# 20160428.net
KiCad netlist of a schematic drawn in Altium Designer
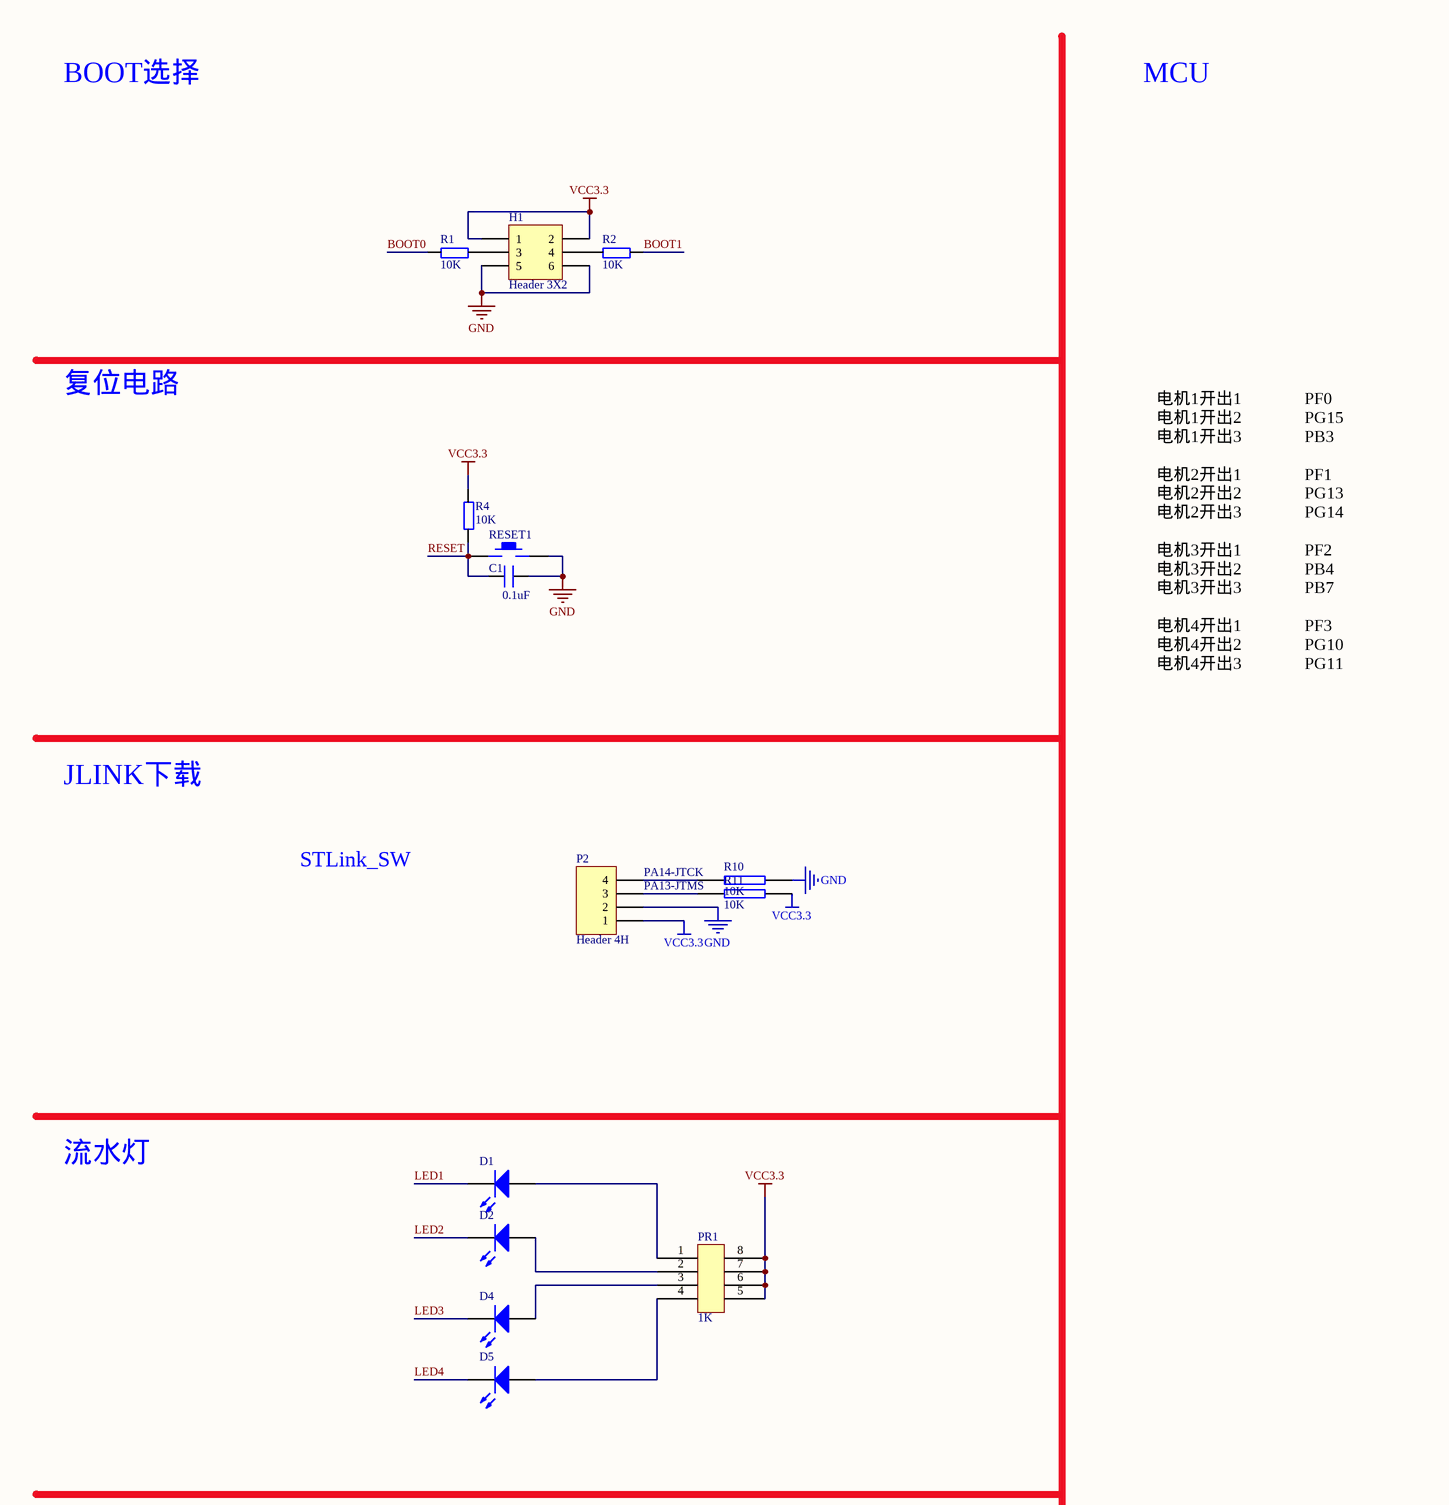
[diagram p0: 主控板20160428.SchDoc, top left]
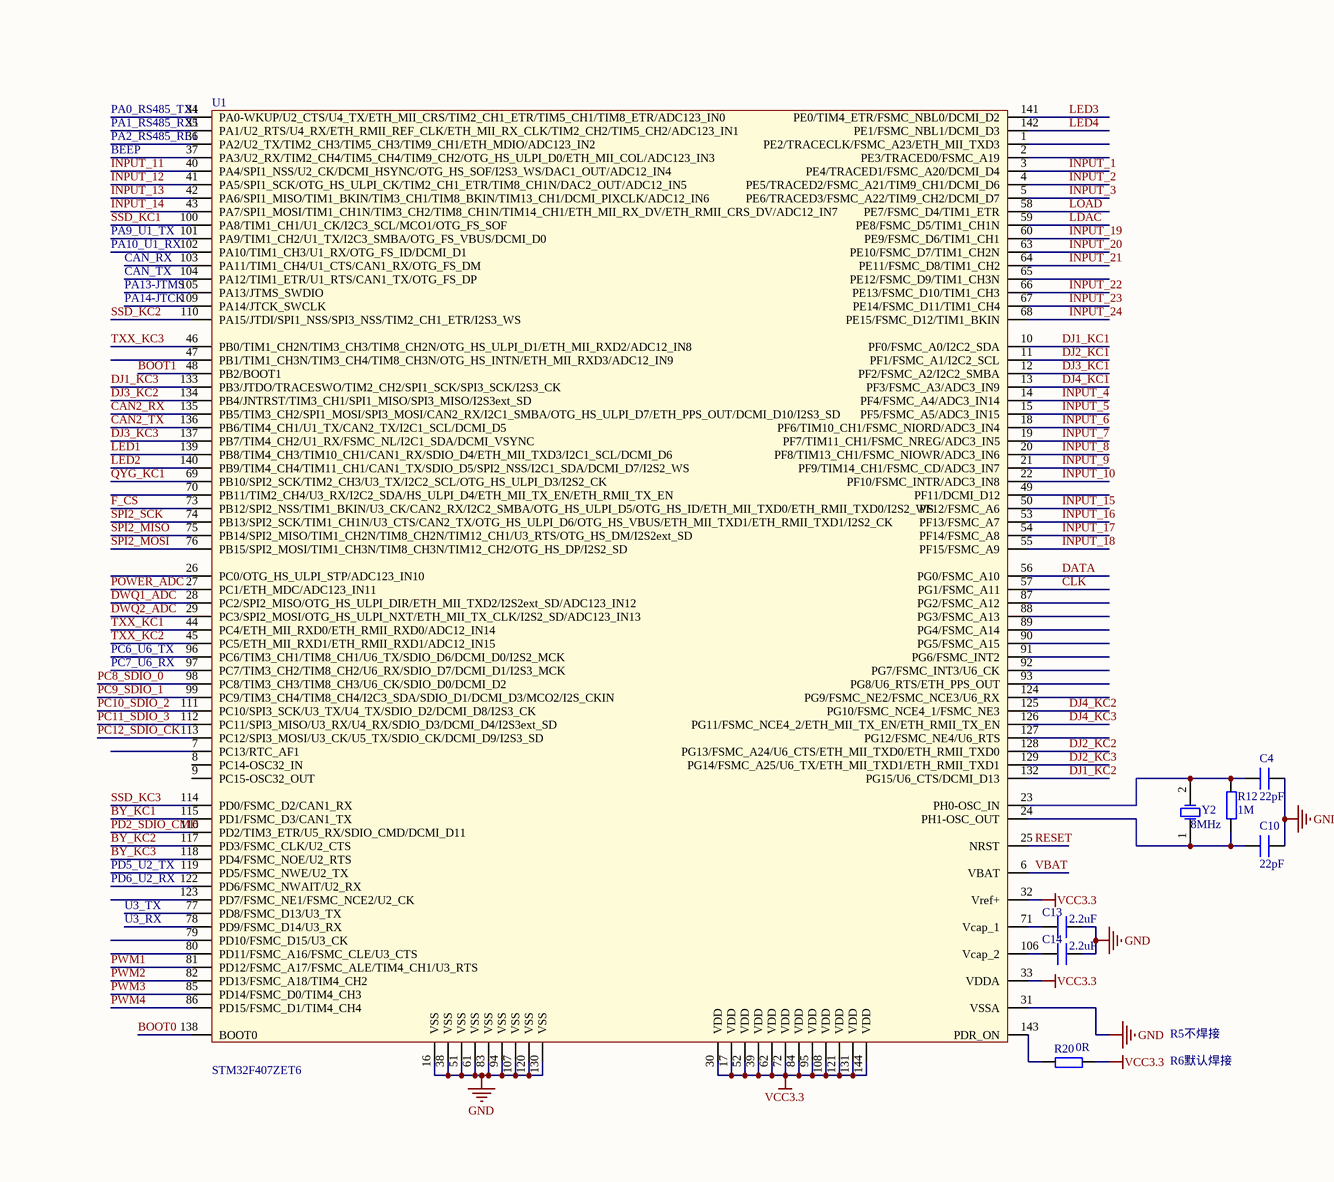
[diagram p1: 主控板20160428.SchDoc, top middle]
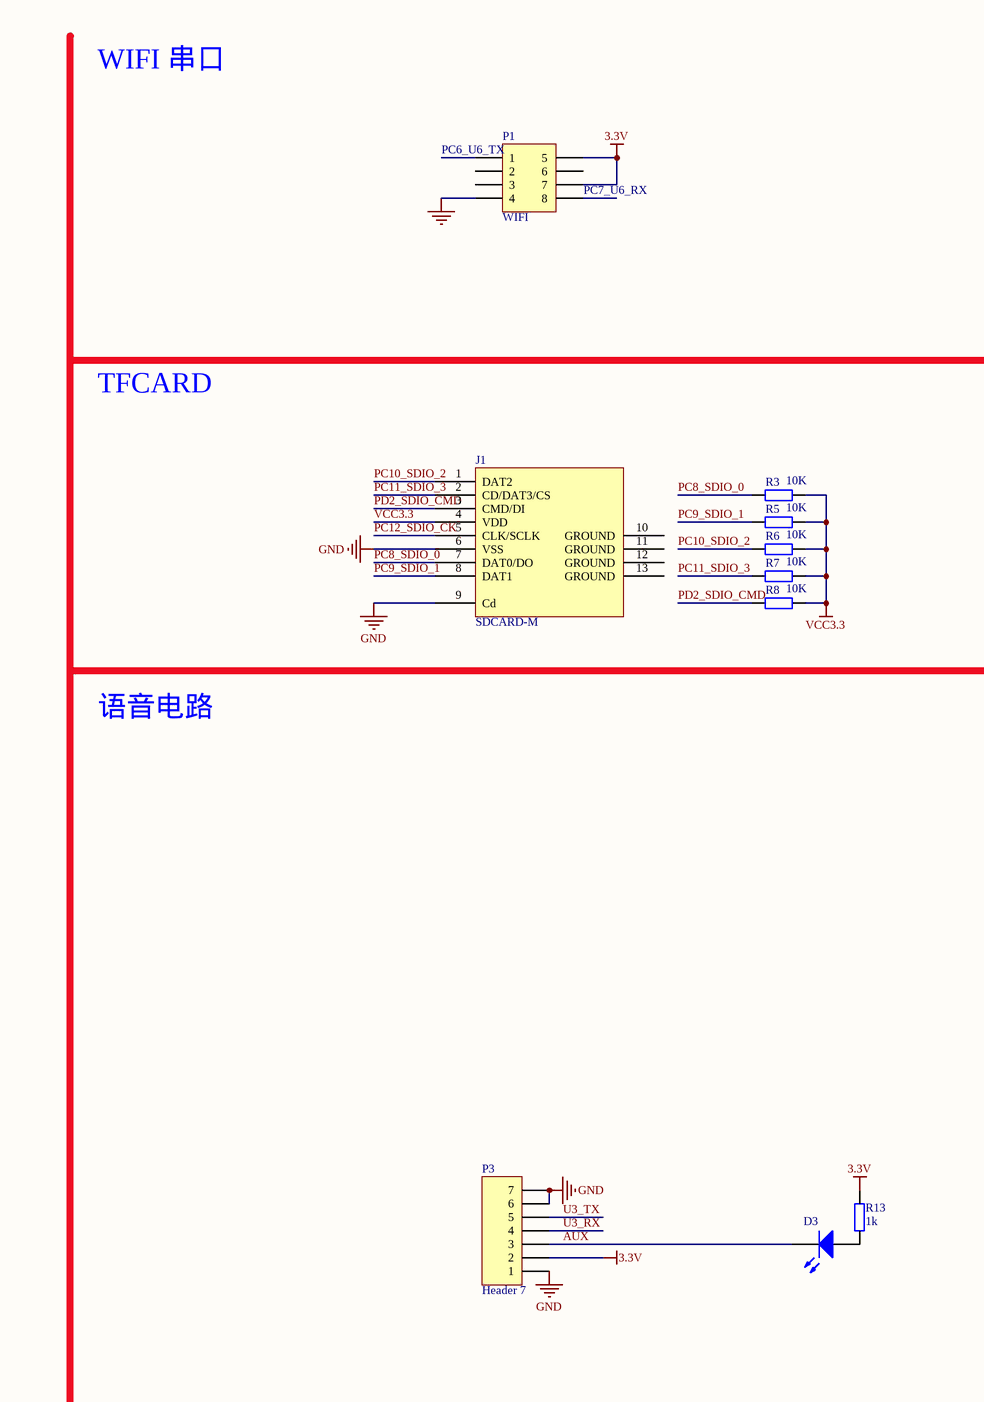
[diagram p2: 主控板20160428.SchDoc, top right]
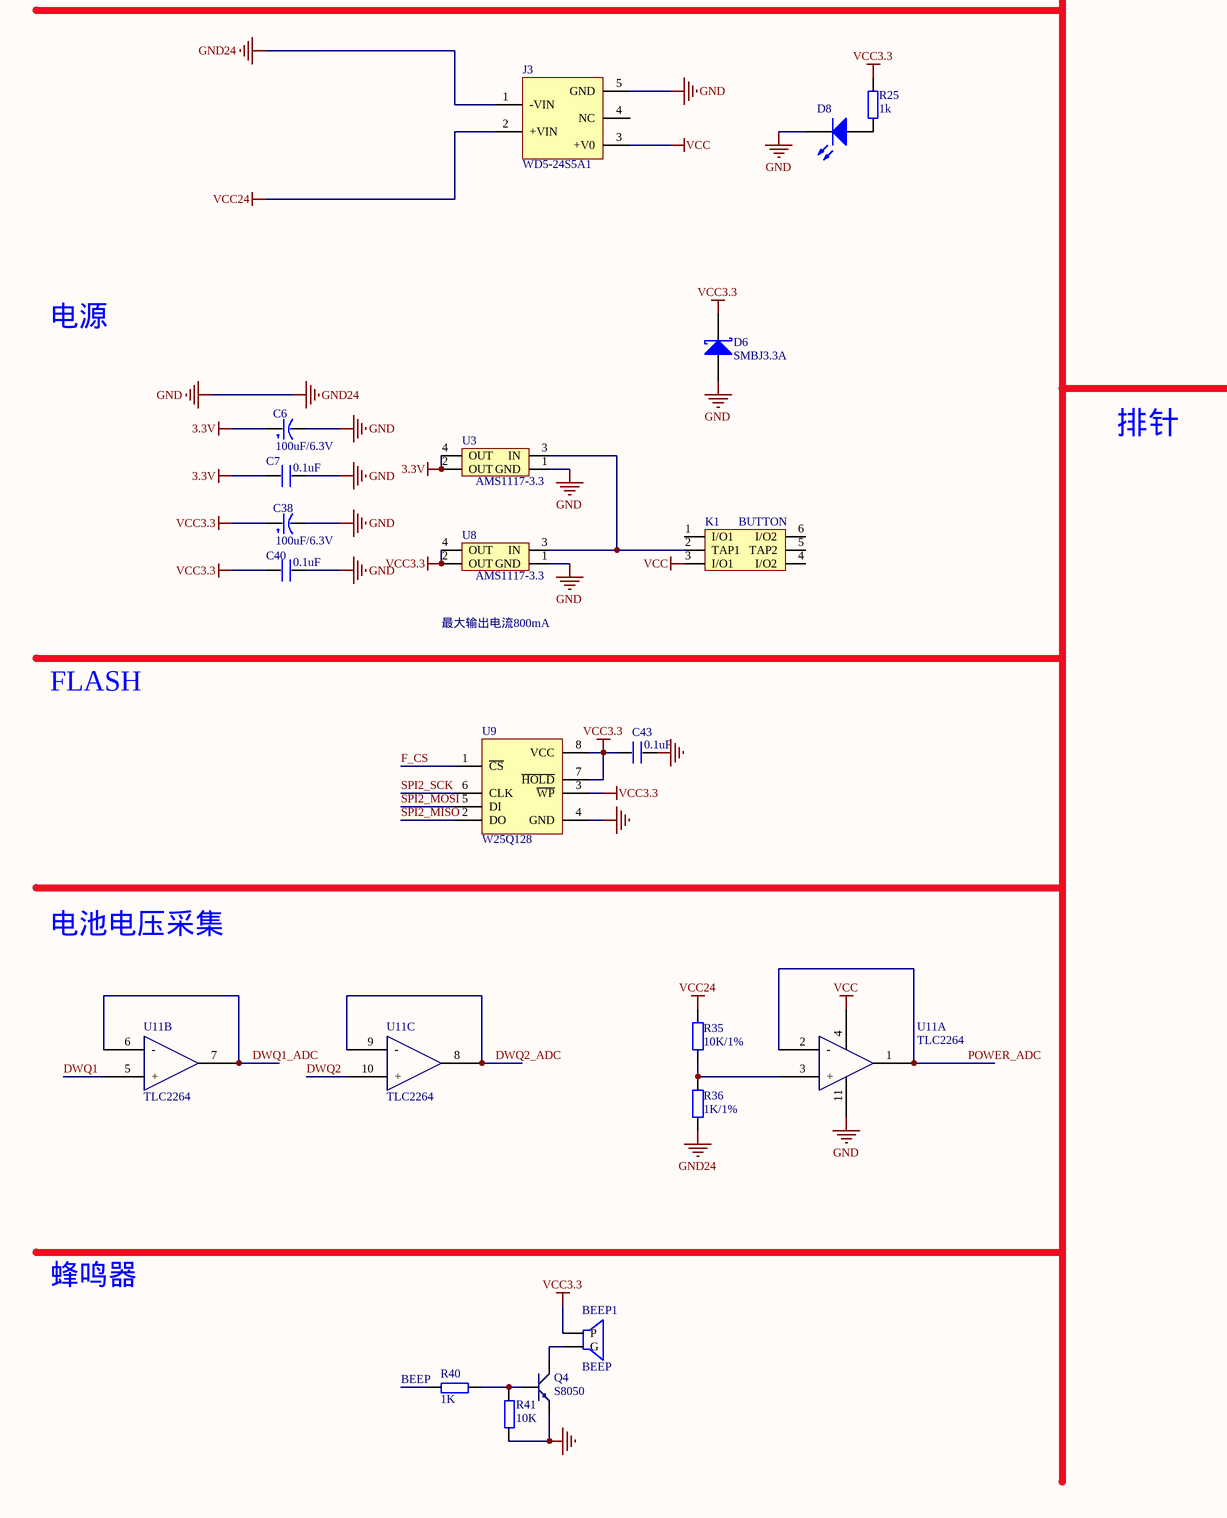
[diagram p3: 主控板20160428.SchDoc, bottom left]
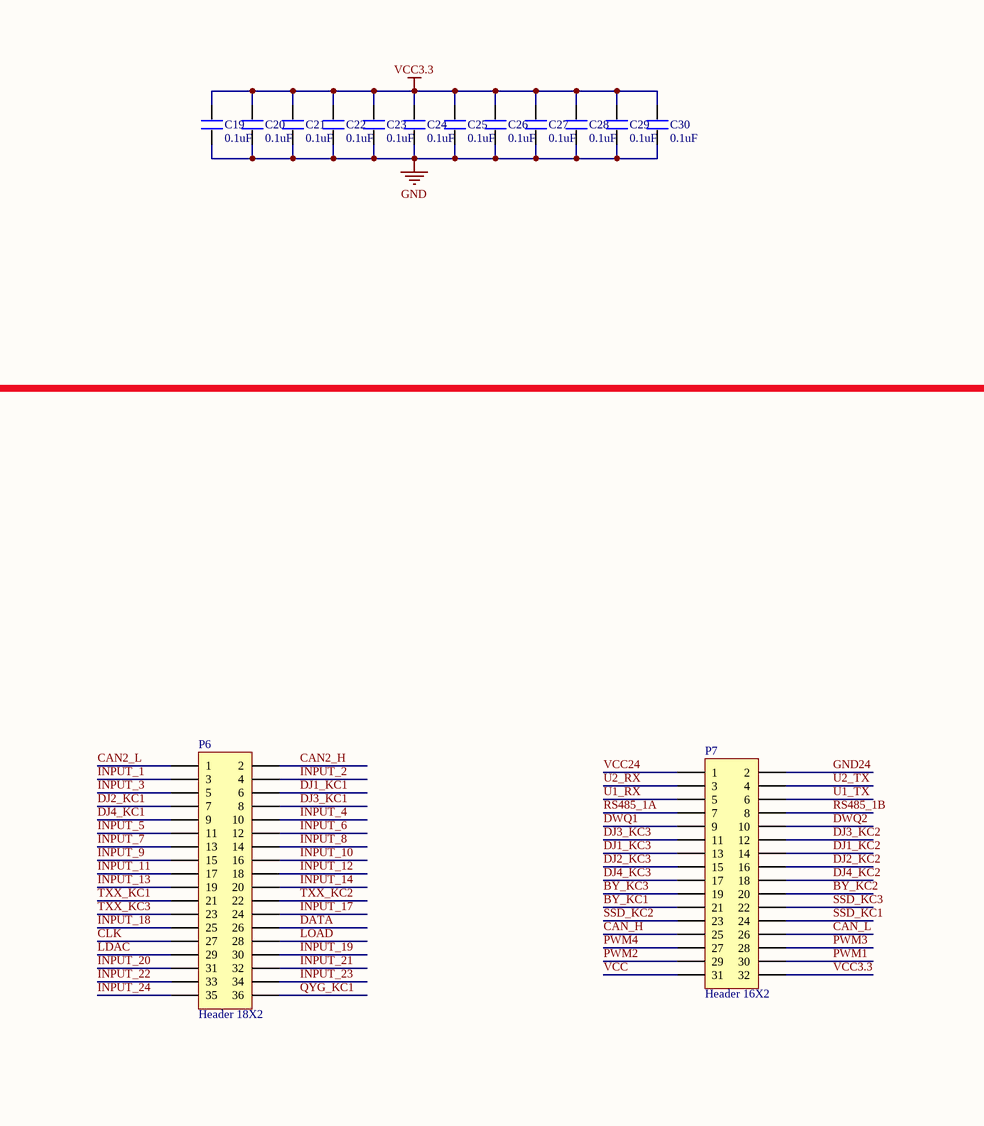
[diagram p4: 主控板20160428.SchDoc, bottom middle]
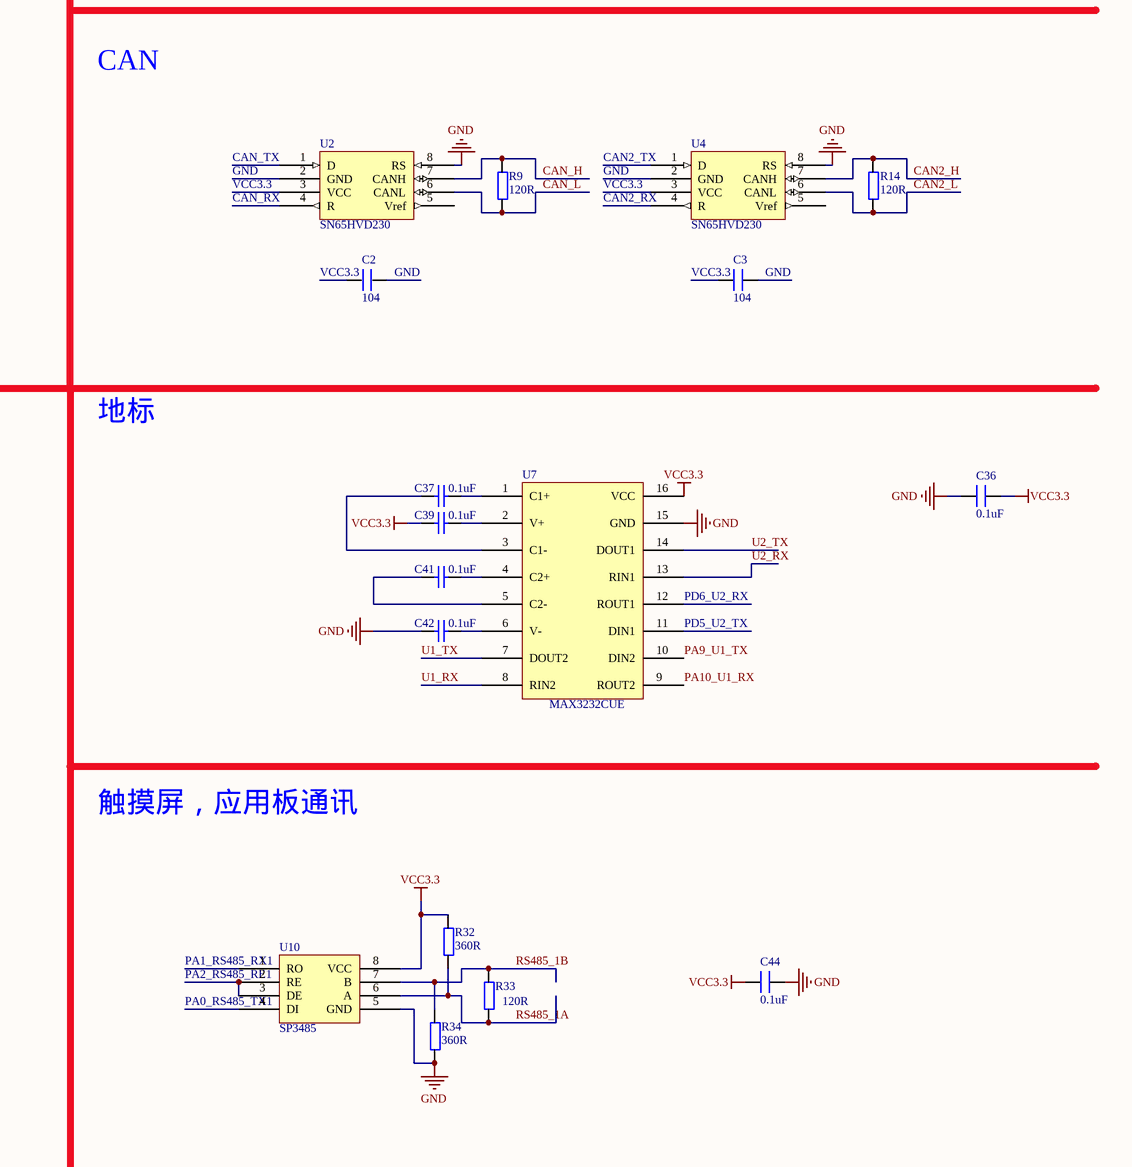
[diagram p5: 主控板20160428.SchDoc, bottom right]

(export (version "E")
  (design (tool "Eeschema 10.0.6"))
  (components
    (comp (ref "BEEP1") (value "BEEP") (footprint "BELL-5") (libsource (lib "WarShip V3_SCH") (part "BEEP")))
    (comp (ref "C1") (value "0.1uF") (footprint "C0805") (libsource (lib "Explorer STM32F407封装库") (part "C")))
    (comp (ref "C2") (value "104") (footprint "C0805") (libsource (lib "Explorer STM32F407封装库") (part "C_3")))
    (comp (ref "C3") (value "104") (footprint "C0805") (libsource (lib "Explorer STM32F407封装库") (part "C_3")))
    (comp (ref "C4")
      (value "22pF")
      (footprint "C0805")
      (libsource (lib "Explorer STM32F407封装库") (part "C_3"))
    )
    (comp (ref "C6") (value "100uF/6.3V") (footprint "3216") (libsource (lib "WarShip V3_SCH") (part "CAP")))
    (comp (ref "C7") (value "0.1uF") (footprint "C0805") (libsource (lib "WarShip V3_SCH") (part "C")))
    (comp (ref "C10")
      (value "22pF")
      (footprint "C0805")
      (libsource (lib "Explorer STM32F407封装库") (part "C_3"))
    )
    (comp (ref "C13")
      (value "2.2uF")
      (footprint "C0805")
      (libsource (lib "Explorer STM32F407封装库") (part "C"))
    )
    (comp (ref "C14")
      (value "2.2uF")
      (footprint "C0805")
      (libsource (lib "Explorer STM32F407封装库") (part "C"))
    )
    (comp (ref "C19") (value "0.1uF") (footprint "C0805") (libsource (lib "WarShip V3_SCH") (part "C")))
    (comp (ref "C20") (value "0.1uF") (footprint "C0805") (libsource (lib "WarShip V3_SCH") (part "C")))
    (comp (ref "C21") (value "0.1uF") (footprint "C0805") (libsource (lib "WarShip V3_SCH") (part "C")))
    (comp (ref "C22") (value "0.1uF") (footprint "C0805") (libsource (lib "WarShip V3_SCH") (part "C")))
    (comp (ref "C23") (value "0.1uF") (footprint "C0805") (libsource (lib "WarShip V3_SCH") (part "C")))
    (comp (ref "C24") (value "0.1uF") (footprint "C0805") (libsource (lib "WarShip V3_SCH") (part "C")))
    (comp (ref "C25") (value "0.1uF") (footprint "C0805") (libsource (lib "WarShip V3_SCH") (part "C")))
    (comp (ref "C26") (value "0.1uF") (footprint "C0805") (libsource (lib "WarShip V3_SCH") (part "C")))
    (comp (ref "C27") (value "0.1uF") (footprint "C0805") (libsource (lib "WarShip V3_SCH") (part "C")))
    (comp (ref "C28") (value "0.1uF") (footprint "C0805") (libsource (lib "WarShip V3_SCH") (part "C")))
    (comp (ref "C29") (value "0.1uF") (footprint "C0805") (libsource (lib "WarShip V3_SCH") (part "C")))
    (comp (ref "C30") (value "0.1uF") (footprint "C0805") (libsource (lib "WarShip V3_SCH") (part "C")))
    (comp (ref "C36")
      (value "0.1uF")
      (footprint "C0805")
      (libsource (lib "Explorer STM32F407封装库") (part "C_2"))
    )
    (comp (ref "C37")
      (value "0.1uF")
      (footprint "C0805")
      (description "Capacitor")
      (fields (field (name "PUBLISHER") "Altium Limited"))
      (libsource (lib "Miscellaneous Devices") (part "Cap"))
    )
    (comp (ref "C38") (value "100uF/6.3V") (footprint "3216") (libsource (lib "WarShip V3_SCH") (part "CAP")))
    (comp (ref "C39")
      (value "0.1uF")
      (footprint "C0805")
      (description "Capacitor")
      (fields (field (name "PUBLISHER") "Altium Limited"))
      (libsource (lib "Miscellaneous Devices") (part "Cap"))
    )
    (comp (ref "C40") (value "0.1uF") (footprint "C0805") (libsource (lib "WarShip V3_SCH") (part "C")))
    (comp (ref "C41")
      (value "0.1uF")
      (footprint "C0805")
      (description "Capacitor")
      (fields (field (name "PUBLISHER") "Altium Limited"))
      (libsource (lib "Miscellaneous Devices") (part "Cap"))
    )
    (comp (ref "C42")
      (value "0.1uF")
      (footprint "C0805")
      (description "Capacitor")
      (fields (field (name "PUBLISHER") "Altium Limited"))
      (libsource (lib "Miscellaneous Devices") (part "Cap"))
    )
    (comp (ref "C43") (value "0.1uF") (footprint "C0805") (libsource (lib "WarShip V3_SCH") (part "C")))
    (comp (ref "C44")
      (value "0.1uF")
      (footprint "C0805")
      (libsource (lib "Explorer STM32F407封装库") (part "C_3"))
    )
    (comp (ref "D1")
      (value "LED0")
      (footprint "LC-0805_LED_S1")
      (description "Typical INFRARED GaAs LED")
      (fields (field (name "PUBLISHER") "Altium Limited"))
      (libsource (lib "继电器板_1") (part "LED0"))
    )
    (comp (ref "D2")
      (value "LED0")
      (footprint "LC-0805_LED_S1")
      (description "Typical INFRARED GaAs LED")
      (fields (field (name "PUBLISHER") "Altium Limited"))
      (libsource (lib "继电器板_1") (part "LED0"))
    )
    (comp (ref "D3")
      (value "LED0")
      (footprint "LC-0805_LED_S1")
      (description "Typical INFRARED GaAs LED")
      (fields (field (name "PUBLISHER") "Altium Limited"))
      (libsource (lib "继电器板_1") (part "LED0"))
    )
    (comp (ref "D4")
      (value "LED0")
      (footprint "LC-0805_LED_S1")
      (description "Typical INFRARED GaAs LED")
      (fields (field (name "PUBLISHER") "Altium Limited"))
      (libsource (lib "继电器板_1") (part "LED0"))
    )
    (comp (ref "D5")
      (value "LED0")
      (footprint "LC-0805_LED_S1")
      (description "Typical INFRARED GaAs LED")
      (fields (field (name "PUBLISHER") "Altium Limited"))
      (libsource (lib "继电器板_1") (part "LED0"))
    )
    (comp (ref "D6")
      (value "SMBJ3.3A")
      (footprint "SMB(DO-214AA)_S1")
      (description "Schottky Rectifier")
      (fields (field (name "PUBLISHER") "Altium Limited"))
      (libsource (lib "Miscellaneous Devices") (part "Diode 18TQ045"))
    )
    (comp (ref "D8")
      (value "LED0")
      (footprint "LC-0805_LED_S1")
      (description "Typical INFRARED GaAs LED")
      (fields (field (name "PUBLISHER") "Altium Limited"))
      (libsource (lib "继电器板_1") (part "LED0"))
    )
    (comp (ref "H1")
      (value "Header 3X2")
      (footprint "HDR2X3")
      (description "Header, 3-Pin, Dual row")
      (fields (field (name "PUBLISHER") "Altium Limited"))
      (libsource (lib "Explorer STM32F407封装库") (part "Header 3X2"))
    )
    (comp (ref "J1")
      (value "SDCARD-M")
      (footprint "SDCARD-M")
      (description "TF卡槽")
      (libsource (lib "fszhang") (part "SDCARD-M"))
    )
    (comp (ref "J3")
      (value "WD5-24S5A1")
      (footprint "WD5-24S3V3")
      (libsource (lib "*") (part "WD5-24S3V3A1"))
    )
    (comp (ref "K1")
      (value "BUTTON")
      (footprint "BTN8.5*8.5")
      (libsource (lib "WarShip V3_SCH") (part "BUTTON"))
    )
    (comp (ref "P1")
      (value "WIFI")
      (footprint "HDR2X4_CEN")
      (description "Header, 4-Pin, Dual row")
      (fields (field (name "PUBLISHER") "Altium Limited"))
      (libsource (lib "Miscellaneous Connectors") (part "Header 4X2A"))
    )
    (comp (ref "P2")
      (value "Header 4H")
      (footprint "IDE4")
      (description "Header, 4-Pin, Right Angle")
      (fields (field (name "PUBLISHER") "Altium Limited"))
      (libsource (lib "Miscellaneous Connectors") (part "Header 4H"))
    )
    (comp (ref "P3")
      (value "Header 7")
      (footprint "AS50-T27")
      (description "Header, 7-Pin")
      (fields (field (name "PUBLISHER") "Altium Limited"))
      (libsource (lib "Miscellaneous Connectors") (part "Header 7"))
    )
    (comp (ref "P6")
      (value "Header 18X2")
      (footprint "HDR2X18")
      (description "Header, 18-Pin, Dual row")
      (fields (field (name "PUBLISHER") "Altium Limited"))
      (libsource (lib "Miscellaneous Connectors") (part "Header 18X2"))
    )
    (comp (ref "P7")
      (value "Header 16X2")
      (footprint "HDR2X16")
      (description "Header, 16-Pin, Dual row")
      (fields (field (name "PUBLISHER") "Altium Limited"))
      (libsource (lib "Miscellaneous Connectors") (part "Header 16X2"))
    )
    (comp (ref "PR1") (value "1K") (footprint "TPPZ") (libsource (lib "EXPLORER") (part "PZ")))
    (comp (ref "Q4")
      (value "S8050")
      (footprint "SOT-23R")
      (description "8050/BCW846/BCW847")
      (libsource (lib "WarShip V3_SCH") (part "NPN"))
    )
    (comp (ref "R1") (value "10K") (footprint "0805") (libsource (lib "Explorer STM32F407封装库") (part "R_1")))
    (comp (ref "R2") (value "10K") (footprint "0805") (libsource (lib "Explorer STM32F407封装库") (part "R_1")))
    (comp (ref "R3")
      (value "10K")
      (footprint "0805")
      (description "贴片电阻")
      (fields (field (name "PUBLISHER") "Altium Limited"))
      (libsource (lib "fszhang") (part "Res1"))
    )
    (comp (ref "R4") (value "10K") (footprint "0805") (libsource (lib "Explorer STM32F407封装库") (part "R_2")))
    (comp (ref "R5")
      (value "10K")
      (footprint "0805")
      (description "贴片电阻")
      (fields (field (name "PUBLISHER") "Altium Limited"))
      (libsource (lib "fszhang") (part "Res1"))
    )
    (comp (ref "R6")
      (value "10K")
      (footprint "0805")
      (description "贴片电阻")
      (fields (field (name "PUBLISHER") "Altium Limited"))
      (libsource (lib "fszhang") (part "Res1"))
    )
    (comp (ref "R7")
      (value "10K")
      (footprint "0805")
      (description "贴片电阻")
      (fields (field (name "PUBLISHER") "Altium Limited"))
      (libsource (lib "fszhang") (part "Res1"))
    )
    (comp (ref "R8")
      (value "10K")
      (footprint "0805")
      (description "贴片电阻")
      (fields (field (name "PUBLISHER") "Altium Limited"))
      (libsource (lib "fszhang") (part "Res1"))
    )
    (comp (ref "R9") (value "120R") (footprint "0805") (libsource (lib "Explorer STM32F407封装库") (part "R_2")))
    (comp (ref "R10") (value "10K") (footprint "0805") (libsource (lib "*") (part "RES2")))
    (comp (ref "R11") (value "10K") (footprint "0805") (libsource (lib "*") (part "RES2")))
    (comp (ref "R12") (value "1M") (footprint "0805") (libsource (lib "Explorer STM32F407封装库") (part "R")))
    (comp (ref "R13") (value "1k") (footprint "0805") (libsource (lib "Explorer STM32F407封装库") (part "R_2")))
    (comp (ref "R14")
      (value "120R")
      (footprint "0805")
      (libsource (lib "Explorer STM32F407封装库") (part "R_2"))
    )
    (comp (ref "R20") (value "0R") (footprint "0805") (libsource (lib "Explorer STM32F407封装库") (part "R_2")))
    (comp (ref "R25") (value "1k") (footprint "0805") (libsource (lib "Explorer STM32F407封装库") (part "R_2")))
    (comp (ref "R32")
      (value "360R")
      (footprint "0805")
      (libsource (lib "Explorer STM32F407封装库") (part "R_2"))
    )
    (comp (ref "R33")
      (value "120R")
      (footprint "0805")
      (libsource (lib "Explorer STM32F407封装库") (part "R_2"))
    )
    (comp (ref "R34")
      (value "360R")
      (footprint "0805")
      (libsource (lib "Explorer STM32F407封装库") (part "R_2"))
    )
    (comp (ref "R35")
      (value "10K/1%")
      (footprint "0805")
      (description "Resistor")
      (fields (field (name "PUBLISHER") "Altium Limited"))
      (libsource (lib "Miscellaneous Devices") (part "Res2"))
    )
    (comp (ref "R36")
      (value "1K/1%")
      (footprint "0805")
      (description "Resistor")
      (fields (field (name "PUBLISHER") "Altium Limited"))
      (libsource (lib "Miscellaneous Devices") (part "Res2"))
    )
    (comp (ref "R40") (value "1K") (footprint "0805") (libsource (lib "WarShip V3_SCH") (part "R")))
    (comp (ref "R41") (value "10K") (footprint "0805") (libsource (lib "WarShip V3_SCH") (part "R")))
    (comp (ref "RESET1")
      (value "KEY_M")
      (footprint "SW_PB2_A1")
      (libsource (lib "Explorer STM32F407封装库") (part "KEY_M"))
    )
    (comp (ref "U1")
      (value "STM32F407ZET6")
      (footprint "LQFP144")
      (libsource (lib "Explorer STM32F407封装库") (part "STM32F407ZET6"))
    )
    (comp (ref "U2")
      (value "SN65HVD230")
      (footprint "LC-SOIC-8_150mil")
      (libsource (lib "Explorer STM32F407封装库") (part "SN65HVD230D"))
    )
    (comp (ref "U3")
      (value "AMS1117-3.3")
      (footprint "SOT-223")
      (libsource (lib "WarShip V3_SCH") (part "AMS1117"))
    )
    (comp (ref "U4")
      (value "SN65HVD230")
      (footprint "LC-SOIC-8_150mil")
      (libsource (lib "Explorer STM32F407封装库") (part "SN65HVD230D"))
    )
    (comp (ref "U7")
      (value "MAX3232CUE")
      (footprint "SO-16")
      (libsource (lib "Smart_board_v1") (part "MAX3232CUE"))
    )
    (comp (ref "U8")
      (value "AMS1117-3.3")
      (footprint "SOT-223")
      (libsource (lib "WarShip V3_SCH") (part "AMS1117"))
    )
    (comp (ref "U9")
      (value "W25Q128")
      (footprint "SOIC8_W")
      (description "SPI FLASH")
      (libsource (lib "fszhang") (part "W25QXX"))
    )
    (comp (ref "U10") (value "SP3485") (footprint "SO-8") (libsource (lib "Schlib1") (part "SP3485")))
    (comp (ref "U11") (value "TLC2264") (footprint "SO-14") (libsource (lib "EXPLORER") (part "TLC2264")))
    (comp (ref "Y2")
      (value "8MHz")
      (footprint "XTAL_US")
      (description "Crystal Oscillator")
      (fields (field (name "PUBLISHER") "Altium Limited"))
      (libsource (lib "Explorer STM32F407封装库") (part "XTAL"))
    )
  )
  (nets
    (net (code "1") (name "/AUX") (class "Default")
      (node (ref "D3") (pin "K") (pinfunction "K_K") (pintype "passive"))
      (node (ref "P3") (pin "3") (pinfunction "3_3") (pintype "passive"))
    )
    (net (code "2") (name "/BEEP") (class "Default")
      (node (ref "R40") (pin "1") (pintype "passive"))
      (node (ref "U1") (pin "37") (pinfunction "PA3/U2_RX/TIM2_CH4/TIM5_CH4/TIM9_CH2/OTG_HS_ULPI_D0/ETH_MII_COL/ADC123_IN3_37") (pintype "passive"))
    )
    (net (code "3") (name "/BOOT0") (class "Default")
      (node (ref "R1") (pin "1") (pintype "passive"))
      (node (ref "U1") (pin "138") (pinfunction "BOOT0_138") (pintype "passive"))
    )
    (net (code "4") (name "/BOOT1") (class "Default")
      (node (ref "R2") (pin "2") (pintype "passive"))
      (node (ref "U1") (pin "48") (pinfunction "PB2/BOOT1_48") (pintype "passive"))
    )
    (net (code "5") (name "/BY_KC1") (class "Default")
      (node (ref "P7") (pin "21") (pinfunction "21_21") (pintype "passive"))
      (node (ref "U1") (pin "115") (pinfunction "PD1/FSMC_D3/CAN1_TX_115") (pintype "passive"))
    )
    (net (code "6") (name "/BY_KC2") (class "Default")
      (node (ref "P7") (pin "20") (pinfunction "20_20") (pintype "passive"))
      (node (ref "U1") (pin "117") (pinfunction "PD3/FSMC_CLK/U2_CTS_117") (pintype "passive"))
    )
    (net (code "7") (name "/BY_KC3") (class "Default")
      (node (ref "P7") (pin "19") (pinfunction "19_19") (pintype "passive"))
      (node (ref "U1") (pin "118") (pinfunction "PD4/FSMC_NOE/U2_RTS_118") (pintype "passive"))
    )
    (net (code "8") (name "/CAN2_H") (class "Default")
      (node (ref "P6") (pin "2") (pinfunction "2_2") (pintype "passive"))
      (node (ref "R14") (pin "2") (pintype "passive"))
      (node (ref "U4") (pin "7") (pinfunction "CANH_7") (pintype "bidirectional"))
    )
    (net (code "9") (name "/CAN2_L") (class "Default")
      (node (ref "P6") (pin "1") (pinfunction "1_1") (pintype "passive"))
      (node (ref "R14") (pin "1") (pintype "passive"))
      (node (ref "U4") (pin "6") (pinfunction "CANL_6") (pintype "bidirectional"))
    )
    (net (code "10") (name "/CAN2_RX") (class "Default")
      (node (ref "U1") (pin "135") (pinfunction "PB5/TIM3_CH2/SPI1_MOSI/SPI3_MOSI/CAN2_RX/I2C1_SMBA/OTG_HS_ULPI_D7/ETH_PPS_OUT/DCMI_D10/I2S3_SD_135") (pintype "passive"))
      (node (ref "U4") (pin "4") (pinfunction "R_4") (pintype "output"))
    )
    (net (code "11") (name "/CAN2_TX") (class "Default")
      (node (ref "U1") (pin "136") (pinfunction "PB6/TIM4_CH1/U1_TX/CAN2_TX/I2C1_SCL/DCMI_D5_136") (pintype "passive"))
      (node (ref "U4") (pin "1") (pinfunction "D_1") (pintype "input"))
    )
    (net (code "12") (name "/CAN_H") (class "Default")
      (node (ref "P7") (pin "25") (pinfunction "25_25") (pintype "passive"))
      (node (ref "R9") (pin "2") (pintype "passive"))
      (node (ref "U2") (pin "7") (pinfunction "CANH_7") (pintype "bidirectional"))
    )
    (net (code "13") (name "/CAN_L") (class "Default")
      (node (ref "P7") (pin "26") (pinfunction "26_26") (pintype "passive"))
      (node (ref "R9") (pin "1") (pintype "passive"))
      (node (ref "U2") (pin "6") (pinfunction "CANL_6") (pintype "bidirectional"))
    )
    (net (code "14") (name "/CAN_RX") (class "Default")
      (node (ref "U1") (pin "103") (pinfunction "PA11/TIM1_CH4/U1_CTS/CAN1_RX/OTG_FS_DM_103") (pintype "passive"))
      (node (ref "U2") (pin "4") (pinfunction "R_4") (pintype "output"))
    )
    (net (code "15") (name "/CAN_TX") (class "Default")
      (node (ref "U1") (pin "104") (pinfunction "PA12/TIM1_ETR/U1_RTS/CAN1_TX/OTG_FS_DP_104") (pintype "passive"))
      (node (ref "U2") (pin "1") (pinfunction "D_1") (pintype "input"))
    )
    (net (code "16") (name "/CLK") (class "Default")
      (node (ref "P6") (pin "27") (pinfunction "27_27") (pintype "passive"))
      (node (ref "U1") (pin "57") (pinfunction "PG1/FSMC_A11_57") (pintype "passive"))
    )
    (net (code "17") (name "/DATA") (class "Default")
      (node (ref "P6") (pin "26") (pinfunction "26_26") (pintype "passive"))
      (node (ref "U1") (pin "56") (pinfunction "PG0/FSMC_A10_56") (pintype "passive"))
    )
    (net (code "18") (name "/DJ1_KC1") (class "Default")
      (node (ref "P6") (pin "6") (pinfunction "6_6") (pintype "passive"))
      (node (ref "U1") (pin "10") (pinfunction "PF0/FSMC_A0/I2C2_SDA_10") (pintype "passive"))
    )
    (net (code "19") (name "/DJ1_KC2") (class "Default")
      (node (ref "P7") (pin "14") (pinfunction "14_14") (pintype "passive"))
      (node (ref "U1") (pin "132") (pinfunction "PG15/U6_CTS/DCMI_D13_132") (pintype "passive"))
    )
    (net (code "20") (name "/DJ1_KC3") (class "Default")
      (node (ref "P7") (pin "13") (pinfunction "13_13") (pintype "passive"))
      (node (ref "U1") (pin "133") (pinfunction "PB3/JTDO/TRACESWO/TIM2_CH2/SPI1_SCK/SPI3_SCK/I2S3_CK_133") (pintype "passive"))
    )
    (net (code "21") (name "/DJ2_KC1") (class "Default")
      (node (ref "P6") (pin "7") (pinfunction "7_7") (pintype "passive"))
      (node (ref "U1") (pin "11") (pinfunction "PF1/FSMC_A1/I2C2_SCL_11") (pintype "passive"))
    )
    (net (code "22") (name "/DJ2_KC2") (class "Default")
      (node (ref "P7") (pin "16") (pinfunction "16_16") (pintype "passive"))
      (node (ref "U1") (pin "128") (pinfunction "PG13/FSMC_A24/U6_CTS/ETH_MII_TXD0/ETH_RMII_TXD0_128") (pintype "passive"))
    )
    (net (code "23") (name "/DJ2_KC3") (class "Default")
      (node (ref "P7") (pin "15") (pinfunction "15_15") (pintype "passive"))
      (node (ref "U1") (pin "129") (pinfunction "PG14/FSMC_A25/U6_TX/ETH_MII_TXD1/ETH_RMII_TXD1_129") (pintype "passive"))
    )
    (net (code "24") (name "/DJ3_KC1") (class "Default")
      (node (ref "P6") (pin "8") (pinfunction "8_8") (pintype "passive"))
      (node (ref "U1") (pin "12") (pinfunction "PF2/FSMC_A2/I2C2_SMBA_12") (pintype "passive"))
    )
    (net (code "25") (name "/DJ3_KC2") (class "Default")
      (node (ref "P7") (pin "12") (pinfunction "12_12") (pintype "passive"))
      (node (ref "U1") (pin "134") (pinfunction "PB4/JNTRST/TIM3_CH1/SPI1_MISO/SPI3_MISO/I2S3ext_SD_134") (pintype "passive"))
    )
    (net (code "26") (name "/DJ3_KC3") (class "Default")
      (node (ref "P7") (pin "11") (pinfunction "11_11") (pintype "passive"))
      (node (ref "U1") (pin "137") (pinfunction "PB7/TIM4_CH2/U1_RX/FSMC_NL/I2C1_SDA/DCMI_VSYNC_137") (pintype "passive"))
    )
    (net (code "27") (name "/DJ4_KC1") (class "Default")
      (node (ref "P6") (pin "9") (pinfunction "9_9") (pintype "passive"))
      (node (ref "U1") (pin "13") (pinfunction "PF3/FSMC_A3/ADC3_IN9_13") (pintype "passive"))
    )
    (net (code "28") (name "/DJ4_KC2") (class "Default")
      (node (ref "P7") (pin "18") (pinfunction "18_18") (pintype "passive"))
      (node (ref "U1") (pin "125") (pinfunction "PG10/FSMC_NCE4_1/FSMC_NE3_125") (pintype "passive"))
    )
    (net (code "29") (name "/DJ4_KC3") (class "Default")
      (node (ref "P7") (pin "17") (pinfunction "17_17") (pintype "passive"))
      (node (ref "U1") (pin "126") (pinfunction "PG11/FSMC_NCE4_2/ETH_MII_TX_EN/ETH_RMII_TX_EN_126") (pintype "passive"))
    )
    (net (code "30") (name "/DWQ1") (class "Default")
      (node (ref "P7") (pin "9") (pinfunction "9_9") (pintype "passive"))
      (node (ref "U11") (pin "5") (pinfunction "+_5") (pintype "passive"))
    )
    (net (code "31") (name "/DWQ1_ADC") (class "Default")
      (node (ref "U1") (pin "28") (pinfunction "PC2/SPI2_MISO/OTG_HS_ULPI_DIR/ETH_MII_TXD2/I2S2ext_SD/ADC123_IN12_28") (pintype "passive"))
      (node (ref "U11") (pin "6") (pinfunction "-_6") (pintype "passive"))
      (node (ref "U11") (pin "7") (pinfunction "2OUT_7") (pintype "passive"))
    )
    (net (code "32") (name "/DWQ2") (class "Default")
      (node (ref "P7") (pin "10") (pinfunction "10_10") (pintype "passive"))
      (node (ref "U11") (pin "10") (pinfunction "+_10") (pintype "passive"))
    )
    (net (code "33") (name "/DWQ2_ADC") (class "Default")
      (node (ref "U1") (pin "29") (pinfunction "PC3/SPI2_MOSI/OTG_HS_ULPI_NXT/ETH_MII_TX_CLK/I2S2_SD/ADC123_IN13_29") (pintype "passive"))
      (node (ref "U11") (pin "8") (pinfunction "3OUT_8") (pintype "passive"))
      (node (ref "U11") (pin "9") (pinfunction "-_9") (pintype "passive"))
    )
    (net (code "34") (name "/F_CS") (class "Default")
      (node (ref "U1") (pin "73") (pinfunction "PB12/SPI2_NSS/TIM1_BKIN/U3_CK/CAN2_RX/I2C2_SMBA/OTG_HS_ULPI_D5/OTG_HS_ID/ETH_MII_TXD0/ETH_RMII_TXD0/I2S2_WS_73") (pintype "passive"))
      (node (ref "U9") (pin "1") (pinfunction "~{CS}_1") (pintype "passive"))
    )
    (net (code "35") (name "/INPUT_1") (class "Default")
      (node (ref "P6") (pin "3") (pinfunction "3_3") (pintype "passive"))
      (node (ref "U1") (pin "3") (pinfunction "PE4/TRACED1/FSMC_A20/DCMI_D4_3") (pintype "passive"))
    )
    (net (code "36") (name "/INPUT_2") (class "Default")
      (node (ref "P6") (pin "4") (pinfunction "4_4") (pintype "passive"))
      (node (ref "U1") (pin "4") (pinfunction "PE5/TRACED2/FSMC_A21/TIM9_CH1/DCMI_D6_4") (pintype "passive"))
    )
    (net (code "37") (name "/INPUT_3") (class "Default")
      (node (ref "P6") (pin "5") (pinfunction "5_5") (pintype "passive"))
      (node (ref "U1") (pin "5") (pinfunction "PE6/TRACED3/FSMC_A22/TIM9_CH2/DCMI_D7_5") (pintype "passive"))
    )
    (net (code "38") (name "/INPUT_4") (class "Default")
      (node (ref "P6") (pin "10") (pinfunction "10_10") (pintype "passive"))
      (node (ref "U1") (pin "14") (pinfunction "PF4/FSMC_A4/ADC3_IN14_14") (pintype "passive"))
    )
    (net (code "39") (name "/INPUT_5") (class "Default")
      (node (ref "P6") (pin "11") (pinfunction "11_11") (pintype "passive"))
      (node (ref "U1") (pin "15") (pinfunction "PF5/FSMC_A5/ADC3_IN15_15") (pintype "passive"))
    )
    (net (code "40") (name "/INPUT_6") (class "Default")
      (node (ref "P6") (pin "12") (pinfunction "12_12") (pintype "passive"))
      (node (ref "U1") (pin "18") (pinfunction "PF6/TIM10_CH1/FSMC_NIORD/ADC3_IN4_18") (pintype "passive"))
    )
    (net (code "41") (name "/INPUT_7") (class "Default")
      (node (ref "P6") (pin "13") (pinfunction "13_13") (pintype "passive"))
      (node (ref "U1") (pin "19") (pinfunction "PF7/TIM11_CH1/FSMC_NREG/ADC3_IN5_19") (pintype "passive"))
    )
    (net (code "42") (name "/INPUT_8") (class "Default")
      (node (ref "P6") (pin "14") (pinfunction "14_14") (pintype "passive"))
      (node (ref "U1") (pin "20") (pinfunction "PF8/TIM13_CH1/FSMC_NIOWR/ADC3_IN6_20") (pintype "passive"))
    )
    (net (code "43") (name "/INPUT_9") (class "Default")
      (node (ref "P6") (pin "15") (pinfunction "15_15") (pintype "passive"))
      (node (ref "U1") (pin "21") (pinfunction "PF9/TIM14_CH1/FSMC_CD/ADC3_IN7_21") (pintype "passive"))
    )
    (net (code "44") (name "/INPUT_10") (class "Default")
      (node (ref "P6") (pin "16") (pinfunction "16_16") (pintype "passive"))
      (node (ref "U1") (pin "22") (pinfunction "PF10/FSMC_INTR/ADC3_IN8_22") (pintype "passive"))
    )
    (net (code "45") (name "/INPUT_11") (class "Default")
      (node (ref "P6") (pin "17") (pinfunction "17_17") (pintype "passive"))
      (node (ref "U1") (pin "40") (pinfunction "PA4/SPI1_NSS/U2_CK/DCMI_HSYNC/OTG_HS_SOF/I2S3_WS/DAC1_OUT/ADC12_IN4_40") (pintype "passive"))
    )
    (net (code "46") (name "/INPUT_12") (class "Default")
      (node (ref "P6") (pin "18") (pinfunction "18_18") (pintype "passive"))
      (node (ref "U1") (pin "41") (pinfunction "PA5/SPI1_SCK/OTG_HS_ULPI_CK/TIM2_CH1_ETR/TIM8_CH1N/DAC2_OUT/ADC12_IN5_41") (pintype "passive"))
    )
    (net (code "47") (name "/INPUT_13") (class "Default")
      (node (ref "P6") (pin "19") (pinfunction "19_19") (pintype "passive"))
      (node (ref "U1") (pin "42") (pinfunction "PA6/SPI1_MISO/TIM1_BKIN/TIM3_CH1/TIM8_BKIN/TIM13_CH1/DCMI_PIXCLK/ADC12_IN6_42") (pintype "passive"))
    )
    (net (code "48") (name "/INPUT_14") (class "Default")
      (node (ref "P6") (pin "20") (pinfunction "20_20") (pintype "passive"))
      (node (ref "U1") (pin "43") (pinfunction "PA7/SPI1_MOSI/TIM1_CH1N/TIM3_CH2/TIM8_CH1N/TIM14_CH1/ETH_MII_RX_DV/ETH_RMII_CRS_DV/ADC12_IN7_43") (pintype "passive"))
    )
    (net (code "49") (name "/INPUT_15") (class "Default")
      (node (ref "U1") (pin "50") (pinfunction "PF12/FSMC_A6_50") (pintype "passive"))
    )
    (net (code "50") (name "/INPUT_16") (class "Default")
      (node (ref "U1") (pin "53") (pinfunction "PF13/FSMC_A7_53") (pintype "passive"))
    )
    (net (code "51") (name "/INPUT_17") (class "Default")
      (node (ref "P6") (pin "24") (pinfunction "24_24") (pintype "passive"))
      (node (ref "U1") (pin "54") (pinfunction "PF14/FSMC_A8_54") (pintype "passive"))
    )
    (net (code "52") (name "/INPUT_18") (class "Default")
      (node (ref "P6") (pin "25") (pinfunction "25_25") (pintype "passive"))
      (node (ref "U1") (pin "55") (pinfunction "PF15/FSMC_A9_55") (pintype "passive"))
    )
    (net (code "53") (name "/INPUT_19") (class "Default")
      (node (ref "P6") (pin "30") (pinfunction "30_30") (pintype "passive"))
      (node (ref "U1") (pin "60") (pinfunction "PE9/FSMC_D6/TIM1_CH1_60") (pintype "passive"))
    )
    (net (code "54") (name "/INPUT_20") (class "Default")
      (node (ref "P6") (pin "31") (pinfunction "31_31") (pintype "passive"))
      (node (ref "U1") (pin "63") (pinfunction "PE10/FSMC_D7/TIM1_CH2N_63") (pintype "passive"))
    )
    (net (code "55") (name "/INPUT_21") (class "Default")
      (node (ref "P6") (pin "32") (pinfunction "32_32") (pintype "passive"))
      (node (ref "U1") (pin "64") (pinfunction "PE11/FSMC_D8/TIM1_CH2_64") (pintype "passive"))
    )
    (net (code "56") (name "/INPUT_22") (class "Default")
      (node (ref "P6") (pin "33") (pinfunction "33_33") (pintype "passive"))
      (node (ref "U1") (pin "66") (pinfunction "PE13/FSMC_D10/TIM1_CH3_66") (pintype "passive"))
    )
    (net (code "57") (name "/INPUT_23") (class "Default")
      (node (ref "P6") (pin "34") (pinfunction "34_34") (pintype "passive"))
      (node (ref "U1") (pin "67") (pinfunction "PE14/FSMC_D11/TIM1_CH4_67") (pintype "passive"))
    )
    (net (code "58") (name "/INPUT_24") (class "Default")
      (node (ref "P6") (pin "35") (pinfunction "35_35") (pintype "passive"))
      (node (ref "U1") (pin "68") (pinfunction "PE15/FSMC_D12/TIM1_BKIN_68") (pintype "passive"))
    )
    (net (code "59") (name "/LDAC") (class "Default")
      (node (ref "P6") (pin "29") (pinfunction "29_29") (pintype "passive"))
      (node (ref "U1") (pin "59") (pinfunction "PE8/FSMC_D5/TIM1_CH1N_59") (pintype "passive"))
    )
    (net (code "60") (name "/LED1") (class "Default")
      (node (ref "D1") (pin "K") (pinfunction "K_K") (pintype "passive"))
      (node (ref "U1") (pin "139") (pinfunction "PB8/TIM4_CH3/TIM10_CH1/CAN1_RX/SDIO_D4/ETH_MII_TXD3/I2C1_SCL/DCMI_D6_139") (pintype "passive"))
    )
    (net (code "61") (name "/LED2") (class "Default")
      (node (ref "D2") (pin "K") (pinfunction "K_K") (pintype "passive"))
      (node (ref "U1") (pin "140") (pinfunction "PB9/TIM4_CH4/TIM11_CH1/CAN1_TX/SDIO_D5/SPI2_NSS/I2C1_SDA/DCMI_D7/I2S2_WS_140") (pintype "passive"))
    )
    (net (code "62") (name "/LED3") (class "Default")
      (node (ref "D4") (pin "K") (pinfunction "K_K") (pintype "passive"))
      (node (ref "U1") (pin "141") (pinfunction "PE0/TIM4_ETR/FSMC_NBL0/DCMI_D2_141") (pintype "passive"))
    )
    (net (code "63") (name "/LED4") (class "Default")
      (node (ref "D5") (pin "K") (pinfunction "K_K") (pintype "passive"))
      (node (ref "U1") (pin "142") (pinfunction "PE1/FSMC_NBL1/DCMI_D3_142") (pintype "passive"))
    )
    (net (code "64") (name "/LOAD") (class "Default")
      (node (ref "P6") (pin "28") (pinfunction "28_28") (pintype "passive"))
      (node (ref "U1") (pin "58") (pinfunction "PE7/FSMC_D4/TIM1_ETR_58") (pintype "passive"))
    )
    (net (code "65") (name "/PA0_RS485_TX1") (class "Default")
      (node (ref "U1") (pin "34") (pinfunction "PA0-WKUP/U2_CTS/U4_TX/ETH_MII_CRS/TIM2_CH1_ETR/TIM5_CH1/TIM8_ETR/ADC123_IN0_34") (pintype "passive"))
      (node (ref "U10") (pin "4") (pinfunction "DI_4") (pintype "passive"))
    )
    (net (code "66") (name "/PA1_RS485_RX1") (class "Default")
      (node (ref "U1") (pin "35") (pinfunction "PA1/U2_RTS/U4_RX/ETH_RMII_REF_CLK/ETH_MII_RX_CLK/TIM2_CH2/TIM5_CH2/ADC123_IN1_35") (pintype "passive"))
      (node (ref "U10") (pin "1") (pinfunction "RO_1") (pintype "passive"))
    )
    (net (code "67") (name "/PA2_RS485_RE1") (class "Default")
      (node (ref "U1") (pin "36") (pinfunction "PA2/U2_TX/TIM2_CH3/TIM5_CH3/TIM9_CH1/ETH_MDIO/ADC123_IN2_36") (pintype "passive"))
      (node (ref "U10") (pin "2") (pinfunction "RE_2") (pintype "passive"))
      (node (ref "U10") (pin "3") (pinfunction "DE_3") (pintype "passive"))
    )
    (net (code "68") (name "/PA9_U1_TX") (class "Default")
      (node (ref "U1") (pin "101") (pinfunction "PA9/TIM1_CH2/U1_TX/I2C3_SMBA/OTG_FS_VBUS/DCMI_D0_101") (pintype "passive"))
      (node (ref "U7") (pin "10") (pinfunction "DIN2_10") (pintype "passive"))
    )
    (net (code "69") (name "/PA10_U1_RX") (class "Default")
      (node (ref "U1") (pin "102") (pinfunction "PA10/TIM1_CH3/U1_RX/OTG_FS_ID/DCMI_D1_102") (pintype "passive"))
      (node (ref "U7") (pin "9") (pinfunction "ROUT2_9") (pintype "passive"))
    )
    (net (code "70") (name "/PA13-JTMS") (class "Default")
      (node (ref "P2") (pin "3") (pinfunction "3_3") (pintype "passive"))
      (node (ref "R11") (pin "2") (pinfunction "2_2") (pintype "passive"))
      (node (ref "U1") (pin "105") (pinfunction "PA13/JTMS_SWDIO_105") (pintype "passive"))
    )
    (net (code "71") (name "/PA14-JTCK") (class "Default")
      (node (ref "P2") (pin "4") (pinfunction "4_4") (pintype "passive"))
      (node (ref "R10") (pin "2") (pinfunction "2_2") (pintype "passive"))
      (node (ref "U1") (pin "109") (pinfunction "PA14/JTCK_SWCLK_109") (pintype "passive"))
    )
    (net (code "72") (name "/PC6_U6_TX") (class "Default")
      (node (ref "P1") (pin "1") (pinfunction "1_1") (pintype "passive"))
      (node (ref "U1") (pin "96") (pinfunction "PC6/TIM3_CH1/TIM8_CH1/U6_TX/SDIO_D6/DCMI_D0/I2S2_MCK_96") (pintype "passive"))
    )
    (net (code "73") (name "/PC7_U6_RX") (class "Default")
      (node (ref "P1") (pin "8") (pinfunction "8_8") (pintype "passive"))
      (node (ref "U1") (pin "97") (pinfunction "PC7/TIM3_CH2/TIM8_CH2/U6_RX/SDIO_D7/DCMI_D1/I2S3_MCK_97") (pintype "passive"))
    )
    (net (code "74") (name "/PC8_SDIO_0") (class "Default")
      (node (ref "J1") (pin "7") (pinfunction "DAT0/DO_7") (pintype "passive"))
      (node (ref "R3") (pin "1") (pinfunction "1_1") (pintype "passive"))
      (node (ref "U1") (pin "98") (pinfunction "PC8/TIM3_CH3/TIM8_CH3/U6_CK/SDIO_D0/DCMI_D2_98") (pintype "passive"))
    )
    (net (code "75") (name "/PC9_SDIO_1") (class "Default")
      (node (ref "J1") (pin "8") (pinfunction "DAT1_8") (pintype "passive"))
      (node (ref "R5") (pin "1") (pinfunction "1_1") (pintype "passive"))
      (node (ref "U1") (pin "99") (pinfunction "PC9/TIM3_CH4/TIM8_CH4/I2C3_SDA/SDIO_D1/DCMI_D3/MCO2/I2S_CKIN_99") (pintype "passive"))
    )
    (net (code "76") (name "/PC10_SDIO_2") (class "Default")
      (node (ref "J1") (pin "1") (pinfunction "DAT2_1") (pintype "passive"))
      (node (ref "R6") (pin "1") (pinfunction "1_1") (pintype "passive"))
      (node (ref "U1") (pin "111") (pinfunction "PC10/SPI3_SCK/U3_TX/U4_TX/SDIO_D2/DCMI_D8/I2S3_CK_111") (pintype "passive"))
    )
    (net (code "77") (name "/PC11_SDIO_3") (class "Default")
      (node (ref "J1") (pin "2") (pinfunction "CD/DAT3/CS_2") (pintype "passive"))
      (node (ref "R7") (pin "1") (pinfunction "1_1") (pintype "passive"))
      (node (ref "U1") (pin "112") (pinfunction "PC11/SPI3_MISO/U3_RX/U4_RX/SDIO_D3/DCMI_D4/I2S3ext_SD_112") (pintype "passive"))
    )
    (net (code "78") (name "/PC12_SDIO_CK") (class "Default")
      (node (ref "J1") (pin "5") (pinfunction "CLK/SCLK_5") (pintype "passive"))
      (node (ref "U1") (pin "113") (pinfunction "PC12/SPI3_MOSI/U3_CK/U5_TX/SDIO_CK/DCMI_D9/I2S3_SD_113") (pintype "passive"))
    )
    (net (code "79") (name "/PD2_SDIO_CMD") (class "Default")
      (node (ref "J1") (pin "3") (pinfunction "CMD/DI_3") (pintype "passive"))
      (node (ref "R8") (pin "1") (pinfunction "1_1") (pintype "passive"))
      (node (ref "U1") (pin "116") (pinfunction "PD2/TIM3_ETR/U5_RX/SDIO_CMD/DCMI_D11_116") (pintype "passive"))
    )
    (net (code "80") (name "/PD5_U2_TX") (class "Default")
      (node (ref "U1") (pin "119") (pinfunction "PD5/FSMC_NWE/U2_TX_119") (pintype "passive"))
      (node (ref "U7") (pin "11") (pinfunction "DIN1_11") (pintype "passive"))
    )
    (net (code "81") (name "/PD6_U2_RX") (class "Default")
      (node (ref "U1") (pin "122") (pinfunction "PD6/FSMC_NWAIT/U2_RX_122") (pintype "passive"))
      (node (ref "U7") (pin "12") (pinfunction "ROUT1_12") (pintype "passive"))
    )
    (net (code "82") (name "/POWER_ADC") (class "Default")
      (node (ref "U1") (pin "27") (pinfunction "PC1/ETH_MDC/ADC123_IN11_27") (pintype "passive"))
      (node (ref "U11") (pin "1") (pinfunction "1OUT_1") (pintype "passive"))
      (node (ref "U11") (pin "2") (pinfunction "-_2") (pintype "passive"))
    )
    (net (code "83") (name "/PWM1") (class "Default")
      (node (ref "P7") (pin "30") (pinfunction "30_30") (pintype "passive"))
      (node (ref "U1") (pin "81") (pinfunction "PD12/FSMC_A17/FSMC_ALE/TIM4_CH1/U3_RTS_81") (pintype "passive"))
    )
    (net (code "84") (name "/PWM2") (class "Default")
      (node (ref "P7") (pin "29") (pinfunction "29_29") (pintype "passive"))
      (node (ref "U1") (pin "82") (pinfunction "PD13/FSMC_A18/TIM4_CH2_82") (pintype "passive"))
    )
    (net (code "85") (name "/PWM3") (class "Default")
      (node (ref "P7") (pin "28") (pinfunction "28_28") (pintype "passive"))
      (node (ref "U1") (pin "85") (pinfunction "PD14/FSMC_D0/TIM4_CH3_85") (pintype "passive"))
    )
    (net (code "86") (name "/PWM4") (class "Default")
      (node (ref "P7") (pin "27") (pinfunction "27_27") (pintype "passive"))
      (node (ref "U1") (pin "86") (pinfunction "PD15/FSMC_D1/TIM4_CH4_86") (pintype "passive"))
    )
    (net (code "87") (name "/QYG_KC1") (class "Default")
      (node (ref "P6") (pin "36") (pinfunction "36_36") (pintype "passive"))
      (node (ref "U1") (pin "69") (pinfunction "PB10/SPI2_SCK/TIM2_CH3/U3_TX/I2C2_SCL/OTG_HS_ULPI_D3/I2S2_CK_69") (pintype "passive"))
    )
    (net (code "88") (name "/RESET") (class "Default")
      (node (ref "C1") (pin "1") (pintype "passive"))
      (node (ref "R4") (pin "1") (pintype "passive"))
      (node (ref "RESET1") (pin "1") (pinfunction "1_1") (pintype "passive"))
      (node (ref "U1") (pin "25") (pinfunction "NRST_25") (pintype "passive"))
    )
    (net (code "89") (name "/RS485_1A") (class "Default")
      (node (ref "P7") (pin "7") (pinfunction "7_7") (pintype "passive"))
      (node (ref "R32") (pin "1") (pintype "passive"))
      (node (ref "R33") (pin "1") (pintype "passive"))
      (node (ref "U10") (pin "6") (pinfunction "A_6") (pintype "passive"))
    )
    (net (code "90") (name "/RS485_1B") (class "Default")
      (node (ref "P7") (pin "8") (pinfunction "8_8") (pintype "passive"))
      (node (ref "R33") (pin "2") (pintype "passive"))
      (node (ref "R34") (pin "2") (pintype "passive"))
      (node (ref "U10") (pin "7") (pinfunction "B_7") (pintype "passive"))
    )
    (net (code "91") (name "/SPI2_MISO") (class "Default")
      (node (ref "U1") (pin "75") (pinfunction "PB14/SPI2_MISO/TIM1_CH2N/TIM8_CH2N/TIM12_CH1/U3_RTS/OTG_HS_DM/I2S2ext_SD_75") (pintype "passive"))
      (node (ref "U9") (pin "2") (pinfunction "DO_2") (pintype "passive"))
    )
    (net (code "92") (name "/SPI2_MOSI") (class "Default")
      (node (ref "U1") (pin "76") (pinfunction "PB15/SPI2_MOSI/TIM1_CH3N/TIM8_CH3N/TIM12_CH2/OTG_HS_DP/I2S2_SD_76") (pintype "passive"))
      (node (ref "U9") (pin "5") (pinfunction "DI_5") (pintype "passive"))
    )
    (net (code "93") (name "/SPI2_SCK") (class "Default")
      (node (ref "U1") (pin "74") (pinfunction "PB13/SPI2_SCK/TIM1_CH1N/U3_CTS/CAN2_TX/OTG_HS_ULPI_D6/OTG_HS_VBUS/ETH_MII_TXD1/ETH_RMII_TXD1/I2S2_CK_74") (pintype "passive"))
      (node (ref "U9") (pin "6") (pinfunction "CLK_6") (pintype "passive"))
    )
    (net (code "94") (name "/SSD_KC1") (class "Default")
      (node (ref "P7") (pin "24") (pinfunction "24_24") (pintype "passive"))
      (node (ref "U1") (pin "100") (pinfunction "PA8/TIM1_CH1/U1_CK/I2C3_SCL/MCO1/OTG_FS_SOF_100") (pintype "passive"))
    )
    (net (code "95") (name "/SSD_KC2") (class "Default")
      (node (ref "P7") (pin "23") (pinfunction "23_23") (pintype "passive"))
      (node (ref "U1") (pin "110") (pinfunction "PA15/JTDI/SPI1_NSS/SPI3_NSS/TIM2_CH1_ETR/I2S3_WS_110") (pintype "passive"))
    )
    (net (code "96") (name "/SSD_KC3") (class "Default")
      (node (ref "P7") (pin "22") (pinfunction "22_22") (pintype "passive"))
      (node (ref "U1") (pin "114") (pinfunction "PD0/FSMC_D2/CAN1_RX_114") (pintype "passive"))
    )
    (net (code "97") (name "/TXX_KC1") (class "Default")
      (node (ref "P6") (pin "21") (pinfunction "21_21") (pintype "passive"))
      (node (ref "U1") (pin "44") (pinfunction "PC4/ETH_MII_RXD0/ETH_RMII_RXD0/ADC12_IN14_44") (pintype "passive"))
    )
    (net (code "98") (name "/TXX_KC2") (class "Default")
      (node (ref "P6") (pin "22") (pinfunction "22_22") (pintype "passive"))
      (node (ref "U1") (pin "45") (pinfunction "PC5/ETH_MII_RXD1/ETH_RMII_RXD1/ADC12_IN15_45") (pintype "passive"))
    )
    (net (code "99") (name "/TXX_KC3") (class "Default")
      (node (ref "P6") (pin "23") (pinfunction "23_23") (pintype "passive"))
      (node (ref "U1") (pin "46") (pinfunction "PB0/TIM1_CH2N/TIM3_CH3/TIM8_CH2N/OTG_HS_ULPI_D1/ETH_MII_RXD2/ADC12_IN8_46") (pintype "passive"))
    )
    (net (code "100") (name "/U1_RX") (class "Default")
      (node (ref "P7") (pin "5") (pinfunction "5_5") (pintype "passive"))
      (node (ref "U7") (pin "8") (pinfunction "RIN2_8") (pintype "passive"))
    )
    (net (code "101") (name "/U1_TX") (class "Default")
      (node (ref "P7") (pin "6") (pinfunction "6_6") (pintype "passive"))
      (node (ref "U7") (pin "7") (pinfunction "DOUT2_7") (pintype "passive"))
    )
    (net (code "102") (name "/U2_RX") (class "Default")
      (node (ref "P7") (pin "3") (pinfunction "3_3") (pintype "passive"))
      (node (ref "U7") (pin "13") (pinfunction "RIN1_13") (pintype "passive"))
    )
    (net (code "103") (name "/U2_TX") (class "Default")
      (node (ref "P7") (pin "4") (pinfunction "4_4") (pintype "passive"))
      (node (ref "U7") (pin "14") (pinfunction "DOUT1_14") (pintype "passive"))
    )
    (net (code "104") (name "/U3_RX") (class "Default")
      (node (ref "P3") (pin "4") (pinfunction "4_4") (pintype "passive"))
      (node (ref "U1") (pin "78") (pinfunction "PD9/FSMC_D14/U3_RX_78") (pintype "passive"))
    )
    (net (code "105") (name "/U3_TX") (class "Default")
      (node (ref "P3") (pin "5") (pinfunction "5_5") (pintype "passive"))
      (node (ref "U1") (pin "77") (pinfunction "PD8/FSMC_D13/U3_TX_77") (pintype "passive"))
    )
    (net (code "106") (name "/VBAT") (class "Default")
      (node (ref "U1") (pin "6") (pinfunction "VBAT_6") (pintype "passive"))
    )
    (net (code "107") (name "3.3V") (class "Default")
      (node (ref "C6") (pin "1") (pinfunction "VCC_1") (pintype "passive"))
      (node (ref "C7") (pin "2") (pintype "passive"))
      (node (ref "P1") (pin "5") (pinfunction "5_5") (pintype "passive"))
      (node (ref "P1") (pin "7") (pinfunction "7_7") (pintype "passive"))
      (node (ref "P3") (pin "2") (pinfunction "2_2") (pintype "passive"))
      (node (ref "R13") (pin "1") (pintype "passive"))
      (node (ref "U3") (pin "2") (pinfunction "OUT_2") (pintype "passive"))
      (node (ref "U3") (pin "4") (pinfunction "OUT_4") (pintype "passive"))
    )
    (net (code "108") (name "GND") (class "Default")
      (node (ref "C1") (pin "2") (pintype "passive"))
      (node (ref "C10") (pin "1") (pintype "passive"))
      (node (ref "C13") (pin "2") (pintype "passive"))
      (node (ref "C14") (pin "2") (pintype "passive"))
      (node (ref "C19") (pin "1") (pintype "passive"))
      (node (ref "C2") (pin "2") (pintype "passive"))
      (node (ref "C20") (pin "1") (pintype "passive"))
      (node (ref "C21") (pin "1") (pintype "passive"))
      (node (ref "C22") (pin "1") (pintype "passive"))
      (node (ref "C23") (pin "1") (pintype "passive"))
      (node (ref "C24") (pin "1") (pintype "passive"))
      (node (ref "C25") (pin "1") (pintype "passive"))
      (node (ref "C26") (pin "1") (pintype "passive"))
      (node (ref "C27") (pin "1") (pintype "passive"))
      (node (ref "C28") (pin "1") (pintype "passive"))
      (node (ref "C29") (pin "1") (pintype "passive"))
      (node (ref "C3") (pin "2") (pintype "passive"))
      (node (ref "C30") (pin "1") (pintype "passive"))
      (node (ref "C36") (pin "1") (pintype "passive"))
      (node (ref "C38") (pin "2") (pinfunction "GND_2") (pintype "passive"))
      (node (ref "C4") (pin "1") (pintype "passive"))
      (node (ref "C40") (pin "1") (pintype "passive"))
      (node (ref "C42") (pin "2") (pinfunction "2_2") (pintype "passive"))
      (node (ref "C43") (pin "2") (pintype "passive"))
      (node (ref "C44") (pin "2") (pintype "passive"))
      (node (ref "C6") (pin "2") (pinfunction "GND_2") (pintype "passive"))
      (node (ref "C7") (pin "1") (pintype "passive"))
      (node (ref "D6") (pin "2") (pinfunction "A_2") (pintype "passive"))
      (node (ref "D8") (pin "K") (pinfunction "K_K") (pintype "passive"))
      (node (ref "H1") (pin "5") (pinfunction "5_5") (pintype "passive"))
      (node (ref "H1") (pin "6") (pinfunction "6_6") (pintype "passive"))
      (node (ref "J1") (pin "6") (pinfunction "VSS_6") (pintype "passive"))
      (node (ref "J1") (pin "9") (pinfunction "Cd_9") (pintype "passive"))
      (node (ref "J3") (pin "1") (pinfunction "-VIN_1") (pintype "passive"))
      (node (ref "J3") (pin "5") (pinfunction "GND_5") (pintype "passive"))
      (node (ref "P1") (pin "4") (pinfunction "4_4") (pintype "passive"))
      (node (ref "P2") (pin "2") (pinfunction "2_2") (pintype "passive"))
      (node (ref "P3") (pin "1") (pinfunction "1_1") (pintype "passive"))
      (node (ref "P3") (pin "6") (pinfunction "6_6") (pintype "passive"))
      (node (ref "P3") (pin "7") (pinfunction "7_7") (pintype "passive"))
      (node (ref "P7") (pin "2") (pinfunction "2_2") (pintype "passive"))
      (node (ref "Q4") (pin "1") (pinfunction "E_1") (pintype "passive"))
      (node (ref "R10") (pin "1") (pinfunction "1_1") (pintype "passive"))
      (node (ref "R34") (pin "1") (pintype "passive"))
      (node (ref "R36") (pin "1") (pinfunction "1_1") (pintype "passive"))
      (node (ref "R41") (pin "1") (pintype "passive"))
      (node (ref "RESET1") (pin "2") (pinfunction "2_2") (pintype "passive"))
      (node (ref "U1") (pin "107") (pinfunction "VSS_107") (pintype "passive"))
      (node (ref "U1") (pin "120") (pinfunction "VSS_120") (pintype "passive"))
      (node (ref "U1") (pin "130") (pinfunction "VSS_130") (pintype "passive"))
      (node (ref "U1") (pin "16") (pinfunction "VSS_16") (pintype "passive"))
      (node (ref "U1") (pin "31") (pinfunction "VSSA_31") (pintype "passive"))
      (node (ref "U1") (pin "38") (pinfunction "VSS_38") (pintype "passive"))
      (node (ref "U1") (pin "51") (pinfunction "VSS_51") (pintype "passive"))
      (node (ref "U1") (pin "61") (pinfunction "VSS_61") (pintype "passive"))
      (node (ref "U1") (pin "83") (pinfunction "VSS_83") (pintype "passive"))
      (node (ref "U1") (pin "94") (pinfunction "VSS_94") (pintype "passive"))
      (node (ref "U10") (pin "5") (pinfunction "GND_5") (pintype "passive"))
      (node (ref "U11") (pin "11") (pinfunction "GND_11") (pintype "passive"))
      (node (ref "U2") (pin "2") (pinfunction "GND_2") (pintype "power_in"))
      (node (ref "U2") (pin "8") (pinfunction "RS_8") (pintype "input"))
      (node (ref "U3") (pin "1") (pinfunction "GND_1") (pintype "passive"))
      (node (ref "U4") (pin "2") (pinfunction "GND_2") (pintype "power_in"))
      (node (ref "U4") (pin "8") (pinfunction "RS_8") (pintype "input"))
      (node (ref "U7") (pin "15") (pinfunction "GND_15") (pintype "passive"))
      (node (ref "U8") (pin "1") (pinfunction "GND_1") (pintype "passive"))
      (node (ref "U9") (pin "4") (pinfunction "GND_4") (pintype "passive"))
    )
    (net (code "109") (name "Net-(BEEP1-G)") (class "Default")
      (node (ref "BEEP1") (pin "2") (pinfunction "G_2") (pintype "passive"))
      (node (ref "Q4") (pin "3") (pinfunction "C_3") (pintype "passive"))
    )
    (net (code "110") (name "Net-(D1-PadA)") (class "Default")
      (node (ref "D1") (pin "A") (pinfunction "A_A") (pintype "passive"))
      (node (ref "PR1") (pin "1") (pinfunction "1_1") (pintype "passive"))
    )
    (net (code "111") (name "Net-(D2-PadA)") (class "Default")
      (node (ref "D2") (pin "A") (pinfunction "A_A") (pintype "passive"))
      (node (ref "PR1") (pin "2") (pinfunction "2_2") (pintype "passive"))
    )
    (net (code "112") (name "Net-(D3-PadA)") (class "Default")
      (node (ref "D3") (pin "A") (pinfunction "A_A") (pintype "passive"))
      (node (ref "R13") (pin "2") (pintype "passive"))
    )
    (net (code "113") (name "Net-(D4-PadA)") (class "Default")
      (node (ref "D4") (pin "A") (pinfunction "A_A") (pintype "passive"))
      (node (ref "PR1") (pin "3") (pinfunction "3_3") (pintype "passive"))
    )
    (net (code "114") (name "Net-(D5-PadA)") (class "Default")
      (node (ref "D5") (pin "A") (pinfunction "A_A") (pintype "passive"))
      (node (ref "PR1") (pin "4") (pinfunction "4_4") (pintype "passive"))
    )
    (net (code "115") (name "Net-(D8-PadA)") (class "Default")
      (node (ref "D8") (pin "A") (pinfunction "A_A") (pintype "passive"))
      (node (ref "R25") (pin "2") (pintype "passive"))
    )
    (net (code "116") (name "Net-(H1-Pad3)") (class "Default")
      (node (ref "H1") (pin "3") (pinfunction "3_3") (pintype "passive"))
      (node (ref "R1") (pin "2") (pintype "passive"))
    )
    (net (code "117") (name "Net-(H1-Pad4)") (class "Default")
      (node (ref "H1") (pin "4") (pinfunction "4_4") (pintype "passive"))
      (node (ref "R2") (pin "1") (pintype "passive"))
    )
    (net (code "118") (name "Net-(K1-TAP1)") (class "Default")
      (node (ref "K1") (pin "2") (pinfunction "TAP1_2") (pintype "passive"))
      (node (ref "U3") (pin "3") (pinfunction "IN_3") (pintype "passive"))
      (node (ref "U8") (pin "3") (pinfunction "IN_3") (pintype "passive"))
    )
    (net (code "119") (name "Net-(Q4-B)") (class "Default")
      (node (ref "Q4") (pin "2") (pinfunction "B_2") (pintype "passive"))
      (node (ref "R40") (pin "2") (pintype "passive"))
      (node (ref "R41") (pin "2") (pintype "passive"))
    )
    (net (code "120") (name "Net-(U1-PDR_ON)") (class "Default")
      (node (ref "R20") (pin "1") (pintype "passive"))
      (node (ref "U1") (pin "143") (pinfunction "PDR_ON_143") (pintype "passive"))
    )
    (net (code "121") (name "Net-(U1-PH0-OSC_IN)") (class "Default")
      (node (ref "C4") (pin "2") (pintype "passive"))
      (node (ref "R12") (pin "2") (pintype "passive"))
      (node (ref "U1") (pin "23") (pinfunction "PH0-OSC_IN_23") (pintype "passive"))
      (node (ref "Y2") (pin "2") (pinfunction "OSC2_2") (pintype "passive"))
    )
    (net (code "122") (name "Net-(U1-PH1-OSC_OUT)") (class "Default")
      (node (ref "C10") (pin "2") (pintype "passive"))
      (node (ref "R12") (pin "1") (pintype "passive"))
      (node (ref "U1") (pin "24") (pinfunction "PH1-OSC_OUT_24") (pintype "passive"))
      (node (ref "Y2") (pin "1") (pinfunction "OSC1_1") (pintype "passive"))
    )
    (net (code "123") (name "Net-(U1-Vcap_1)") (class "Default")
      (node (ref "C13") (pin "1") (pintype "passive"))
      (node (ref "U1") (pin "71") (pinfunction "Vcap_1_71") (pintype "passive"))
    )
    (net (code "124") (name "Net-(U1-Vcap_2)") (class "Default")
      (node (ref "C14") (pin "1") (pintype "passive"))
      (node (ref "U1") (pin "106") (pinfunction "Vcap_2_106") (pintype "passive"))
    )
    (net (code "125") (name "Net-(U7-C1+)") (class "Default")
      (node (ref "C37") (pin "1") (pinfunction "1_1") (pintype "passive"))
      (node (ref "U7") (pin "1") (pinfunction "C1+_1") (pintype "passive"))
    )
    (net (code "126") (name "Net-(U7-C1-)") (class "Default")
      (node (ref "C37") (pin "2") (pinfunction "2_2") (pintype "passive"))
      (node (ref "U7") (pin "3") (pinfunction "C1-_3") (pintype "passive"))
    )
    (net (code "127") (name "Net-(U7-C2+)") (class "Default")
      (node (ref "C41") (pin "1") (pinfunction "1_1") (pintype "passive"))
      (node (ref "U7") (pin "4") (pinfunction "C2+_4") (pintype "passive"))
    )
    (net (code "128") (name "Net-(U7-C2-)") (class "Default")
      (node (ref "C41") (pin "2") (pinfunction "2_2") (pintype "passive"))
      (node (ref "U7") (pin "5") (pinfunction "C2-_5") (pintype "passive"))
    )
    (net (code "129") (name "Net-(U7-V+)") (class "Default")
      (node (ref "C39") (pin "1") (pinfunction "1_1") (pintype "passive"))
      (node (ref "U7") (pin "2") (pinfunction "V+_2") (pintype "passive"))
    )
    (net (code "130") (name "Net-(U7-V-)") (class "Default")
      (node (ref "C42") (pin "1") (pinfunction "1_1") (pintype "passive"))
      (node (ref "U7") (pin "6") (pinfunction "V-_6") (pintype "passive"))
    )
    (net (code "131") (name "Net-(U11A-+)") (class "Default")
      (node (ref "R35") (pin "1") (pinfunction "1_1") (pintype "passive"))
      (node (ref "R36") (pin "2") (pinfunction "2_2") (pintype "passive"))
      (node (ref "U11") (pin "3") (pinfunction "+_3") (pintype "passive"))
    )
    (net (code "132") (name "VCC") (class "Default")
      (node (ref "J3") (pin "3") (pinfunction "+V0_3") (pintype "passive"))
      (node (ref "K1") (pin "3") (pinfunction "I/O1_3") (pintype "passive"))
      (node (ref "P7") (pin "31") (pinfunction "31_31") (pintype "passive"))
      (node (ref "U11") (pin "4") (pinfunction "VCC_4") (pintype "passive"))
    )
    (net (code "133") (name "VCC3.3") (class "Default")
      (node (ref "BEEP1") (pin "1") (pinfunction "P_1") (pintype "passive"))
      (node (ref "C19") (pin "2") (pintype "passive"))
      (node (ref "C2") (pin "1") (pintype "passive"))
      (node (ref "C20") (pin "2") (pintype "passive"))
      (node (ref "C21") (pin "2") (pintype "passive"))
      (node (ref "C22") (pin "2") (pintype "passive"))
      (node (ref "C23") (pin "2") (pintype "passive"))
      (node (ref "C24") (pin "2") (pintype "passive"))
      (node (ref "C25") (pin "2") (pintype "passive"))
      (node (ref "C26") (pin "2") (pintype "passive"))
      (node (ref "C27") (pin "2") (pintype "passive"))
      (node (ref "C28") (pin "2") (pintype "passive"))
      (node (ref "C29") (pin "2") (pintype "passive"))
      (node (ref "C3") (pin "1") (pintype "passive"))
      (node (ref "C30") (pin "2") (pintype "passive"))
      (node (ref "C36") (pin "2") (pintype "passive"))
      (node (ref "C38") (pin "1") (pinfunction "VCC_1") (pintype "passive"))
      (node (ref "C39") (pin "2") (pinfunction "2_2") (pintype "passive"))
      (node (ref "C40") (pin "2") (pintype "passive"))
      (node (ref "C43") (pin "1") (pintype "passive"))
      (node (ref "C44") (pin "1") (pintype "passive"))
      (node (ref "D6") (pin "1") (pinfunction "K_1") (pintype "passive"))
      (node (ref "H1") (pin "1") (pinfunction "1_1") (pintype "passive"))
      (node (ref "H1") (pin "2") (pinfunction "2_2") (pintype "passive"))
      (node (ref "J1") (pin "4") (pinfunction "VDD_4") (pintype "passive"))
      (node (ref "P2") (pin "1") (pinfunction "1_1") (pintype "passive"))
      (node (ref "P7") (pin "32") (pinfunction "32_32") (pintype "passive"))
      (node (ref "PR1") (pin "5") (pinfunction "5_5") (pintype "passive"))
      (node (ref "PR1") (pin "6") (pinfunction "6_6") (pintype "passive"))
      (node (ref "PR1") (pin "7") (pinfunction "7_7") (pintype "passive"))
      (node (ref "PR1") (pin "8") (pinfunction "8_8") (pintype "passive"))
      (node (ref "R11") (pin "1") (pinfunction "1_1") (pintype "passive"))
      (node (ref "R20") (pin "2") (pintype "passive"))
      (node (ref "R25") (pin "1") (pintype "passive"))
      (node (ref "R3") (pin "2") (pinfunction "2_2") (pintype "passive"))
      (node (ref "R32") (pin "2") (pintype "passive"))
      (node (ref "R4") (pin "2") (pintype "passive"))
      (node (ref "R5") (pin "2") (pinfunction "2_2") (pintype "passive"))
      (node (ref "R6") (pin "2") (pinfunction "2_2") (pintype "passive"))
      (node (ref "R7") (pin "2") (pinfunction "2_2") (pintype "passive"))
      (node (ref "R8") (pin "2") (pinfunction "2_2") (pintype "passive"))
      (node (ref "U1") (pin "108") (pinfunction "VDD_108") (pintype "passive"))
      (node (ref "U1") (pin "121") (pinfunction "VDD_121") (pintype "passive"))
      (node (ref "U1") (pin "131") (pinfunction "VDD_131") (pintype "passive"))
      (node (ref "U1") (pin "144") (pinfunction "VDD_144") (pintype "passive"))
      (node (ref "U1") (pin "17") (pinfunction "VDD_17") (pintype "passive"))
      (node (ref "U1") (pin "30") (pinfunction "VDD_30") (pintype "passive"))
      (node (ref "U1") (pin "32") (pinfunction "Vref+_32") (pintype "passive"))
      (node (ref "U1") (pin "33") (pinfunction "VDDA_33") (pintype "passive"))
      (node (ref "U1") (pin "39") (pinfunction "VDD_39") (pintype "passive"))
      (node (ref "U1") (pin "52") (pinfunction "VDD_52") (pintype "passive"))
      (node (ref "U1") (pin "62") (pinfunction "VDD_62") (pintype "passive"))
      (node (ref "U1") (pin "72") (pinfunction "VDD_72") (pintype "passive"))
      (node (ref "U1") (pin "84") (pinfunction "VDD_84") (pintype "passive"))
      (node (ref "U1") (pin "95") (pinfunction "VDD_95") (pintype "passive"))
      (node (ref "U10") (pin "8") (pinfunction "VCC_8") (pintype "passive"))
      (node (ref "U2") (pin "3") (pinfunction "VCC_3") (pintype "power_in"))
      (node (ref "U4") (pin "3") (pinfunction "VCC_3") (pintype "power_in"))
      (node (ref "U7") (pin "16") (pinfunction "VCC_16") (pintype "passive"))
      (node (ref "U8") (pin "2") (pinfunction "OUT_2") (pintype "passive"))
      (node (ref "U8") (pin "4") (pinfunction "OUT_4") (pintype "passive"))
      (node (ref "U9") (pin "3") (pinfunction "~{WP}_3") (pintype "passive"))
      (node (ref "U9") (pin "7") (pinfunction "~{HOLD}_7") (pintype "passive"))
      (node (ref "U9") (pin "8") (pinfunction "VCC_8") (pintype "passive"))
    )
    (net (code "134") (name "VCC24") (class "Default")
      (node (ref "J3") (pin "2") (pinfunction "+VIN_2") (pintype "passive"))
      (node (ref "P7") (pin "1") (pinfunction "1_1") (pintype "passive"))
      (node (ref "R35") (pin "2") (pinfunction "2_2") (pintype "passive"))
    )
    (net (code "135") (name "unconnected-(J1-GROUND-Pad10)") (class "Default")
      (node (ref "J1") (pin "10") (pinfunction "GROUND_10") (pintype "passive"))
    )
    (net (code "136") (name "unconnected-(J1-GROUND-Pad11)") (class "Default")
      (node (ref "J1") (pin "11") (pinfunction "GROUND_11") (pintype "passive"))
    )
    (net (code "137") (name "unconnected-(J1-GROUND-Pad12)") (class "Default")
      (node (ref "J1") (pin "12") (pinfunction "GROUND_12") (pintype "passive"))
    )
    (net (code "138") (name "unconnected-(J1-GROUND-Pad13)") (class "Default")
      (node (ref "J1") (pin "13") (pinfunction "GROUND_13") (pintype "passive"))
    )
    (net (code "139") (name "unconnected-(J3-NC-Pad4)") (class "Default")
      (node (ref "J3") (pin "4") (pinfunction "NC_4") (pintype "passive"))
    )
    (net (code "140") (name "unconnected-(K1-I{slash}O1-Pad1)") (class "Default")
      (node (ref "K1") (pin "1") (pinfunction "I/O1_1") (pintype "passive"))
    )
    (net (code "141") (name "unconnected-(K1-I{slash}O2-Pad4)") (class "Default")
      (node (ref "K1") (pin "4") (pinfunction "I/O2_4") (pintype "passive"))
    )
    (net (code "142") (name "unconnected-(K1-I{slash}O2-Pad6)") (class "Default")
      (node (ref "K1") (pin "6") (pinfunction "I/O2_6") (pintype "passive"))
    )
    (net (code "143") (name "unconnected-(K1-TAP2-Pad5)") (class "Default")
      (node (ref "K1") (pin "5") (pinfunction "TAP2_5") (pintype "passive"))
    )
    (net (code "144") (name "unconnected-(P1-Pad2)") (class "Default")
      (node (ref "P1") (pin "2") (pinfunction "2_2") (pintype "passive"))
    )
    (net (code "145") (name "unconnected-(P1-Pad3)") (class "Default")
      (node (ref "P1") (pin "3") (pinfunction "3_3") (pintype "passive"))
    )
    (net (code "146") (name "unconnected-(P1-Pad6)") (class "Default")
      (node (ref "P1") (pin "6") (pinfunction "6_6") (pintype "passive"))
    )
    (net (code "147") (name "unconnected-(U1-PB1{slash}TIM1_CH3N{slash}TIM3_CH4{slash}TIM8_CH3N{slash}OTG_HS_INTN{slash}ETH_MII_RXD3{slash}ADC12_IN9-Pad47)") (class "Default")
      (node (ref "U1") (pin "47") (pinfunction "PB1/TIM1_CH3N/TIM3_CH4/TIM8_CH3N/OTG_HS_INTN/ETH_MII_RXD3/ADC12_IN9_47") (pintype "passive"))
    )
    (net (code "148") (name "unconnected-(U1-PB11{slash}TIM2_CH4{slash}U3_RX{slash}I2C2_SDA{slash}HS_ULPI_D4{slash}ETH_MII_TX_EN{slash}ETH_RMII_TX_EN-Pad70)") (class "Default")
      (node (ref "U1") (pin "70") (pinfunction "PB11/TIM2_CH4/U3_RX/I2C2_SDA/HS_ULPI_D4/ETH_MII_TX_EN/ETH_RMII_TX_EN_70") (pintype "passive"))
    )
    (net (code "149") (name "unconnected-(U1-PC0{slash}OTG_HS_ULPI_STP{slash}ADC123_IN10-Pad26)") (class "Default")
      (node (ref "U1") (pin "26") (pinfunction "PC0/OTG_HS_ULPI_STP/ADC123_IN10_26") (pintype "passive"))
    )
    (net (code "150") (name "unconnected-(U1-PC13{slash}RTC_AF1-Pad7)") (class "Default")
      (node (ref "U1") (pin "7") (pinfunction "PC13/RTC_AF1_7") (pintype "passive"))
    )
    (net (code "151") (name "unconnected-(U1-PC14-OSC32_IN-Pad8)") (class "Default")
      (node (ref "U1") (pin "8") (pinfunction "PC14-OSC32_IN_8") (pintype "passive"))
    )
    (net (code "152") (name "unconnected-(U1-PC15-OSC32_OUT-Pad9)") (class "Default")
      (node (ref "U1") (pin "9") (pinfunction "PC15-OSC32_OUT_9") (pintype "passive"))
    )
    (net (code "153") (name "unconnected-(U1-PD7{slash}FSMC_NE1{slash}FSMC_NCE2{slash}U2_CK-Pad123)") (class "Default")
      (node (ref "U1") (pin "123") (pinfunction "PD7/FSMC_NE1/FSMC_NCE2/U2_CK_123") (pintype "passive"))
    )
    (net (code "154") (name "unconnected-(U1-PD10{slash}FSMC_D15{slash}U3_CK-Pad79)") (class "Default")
      (node (ref "U1") (pin "79") (pinfunction "PD10/FSMC_D15/U3_CK_79") (pintype "passive"))
    )
    (net (code "155") (name "unconnected-(U1-PD11{slash}FSMC_A16{slash}FSMC_CLE{slash}U3_CTS-Pad80)") (class "Default")
      (node (ref "U1") (pin "80") (pinfunction "PD11/FSMC_A16/FSMC_CLE/U3_CTS_80") (pintype "passive"))
    )
    (net (code "156") (name "unconnected-(U1-PE2{slash}TRACECLK{slash}FSMC_A23{slash}ETH_MII_TXD3-Pad1)") (class "Default")
      (node (ref "U1") (pin "1") (pinfunction "PE2/TRACECLK/FSMC_A23/ETH_MII_TXD3_1") (pintype "passive"))
    )
    (net (code "157") (name "unconnected-(U1-PE3{slash}TRACED0{slash}FSMC_A19-Pad2)") (class "Default")
      (node (ref "U1") (pin "2") (pinfunction "PE3/TRACED0/FSMC_A19_2") (pintype "passive"))
    )
    (net (code "158") (name "unconnected-(U1-PE12{slash}FSMC_D9{slash}TIM1_CH3N-Pad65)") (class "Default")
      (node (ref "U1") (pin "65") (pinfunction "PE12/FSMC_D9/TIM1_CH3N_65") (pintype "passive"))
    )
    (net (code "159") (name "unconnected-(U1-PF11{slash}DCMI_D12-Pad49)") (class "Default")
      (node (ref "U1") (pin "49") (pinfunction "PF11/DCMI_D12_49") (pintype "passive"))
    )
    (net (code "160") (name "unconnected-(U1-PG2{slash}FSMC_A12-Pad87)") (class "Default")
      (node (ref "U1") (pin "87") (pinfunction "PG2/FSMC_A12_87") (pintype "passive"))
    )
    (net (code "161") (name "unconnected-(U1-PG3{slash}FSMC_A13-Pad88)") (class "Default")
      (node (ref "U1") (pin "88") (pinfunction "PG3/FSMC_A13_88") (pintype "passive"))
    )
    (net (code "162") (name "unconnected-(U1-PG4{slash}FSMC_A14-Pad89)") (class "Default")
      (node (ref "U1") (pin "89") (pinfunction "PG4/FSMC_A14_89") (pintype "passive"))
    )
    (net (code "163") (name "unconnected-(U1-PG5{slash}FSMC_A15-Pad90)") (class "Default")
      (node (ref "U1") (pin "90") (pinfunction "PG5/FSMC_A15_90") (pintype "passive"))
    )
    (net (code "164") (name "unconnected-(U1-PG6{slash}FSMC_INT2-Pad91)") (class "Default")
      (node (ref "U1") (pin "91") (pinfunction "PG6/FSMC_INT2_91") (pintype "passive"))
    )
    (net (code "165") (name "unconnected-(U1-PG7{slash}FSMC_INT3{slash}U6_CK-Pad92)") (class "Default")
      (node (ref "U1") (pin "92") (pinfunction "PG7/FSMC_INT3/U6_CK_92") (pintype "passive"))
    )
    (net (code "166") (name "unconnected-(U1-PG8{slash}U6_RTS{slash}ETH_PPS_OUT-Pad93)") (class "Default")
      (node (ref "U1") (pin "93") (pinfunction "PG8/U6_RTS/ETH_PPS_OUT_93") (pintype "passive"))
    )
    (net (code "167") (name "unconnected-(U1-PG9{slash}FSMC_NE2{slash}FSMC_NCE3{slash}U6_RX-Pad124)") (class "Default")
      (node (ref "U1") (pin "124") (pinfunction "PG9/FSMC_NE2/FSMC_NCE3/U6_RX_124") (pintype "passive"))
    )
    (net (code "168") (name "unconnected-(U1-PG12{slash}FSMC_NE4{slash}U6_RTS-Pad127)") (class "Default")
      (node (ref "U1") (pin "127") (pinfunction "PG12/FSMC_NE4/U6_RTS_127") (pintype "passive"))
    )
    (net (code "169") (name "unconnected-(U2-Vref-Pad5)") (class "Default")
      (node (ref "U2") (pin "5") (pinfunction "Vref_5") (pintype "output"))
    )
    (net (code "170") (name "unconnected-(U4-Vref-Pad5)") (class "Default")
      (node (ref "U4") (pin "5") (pinfunction "Vref_5") (pintype "output"))
    )
  )
)
